# User_IO.net
KiCad netlist of a schematic drawn in Altium Designer
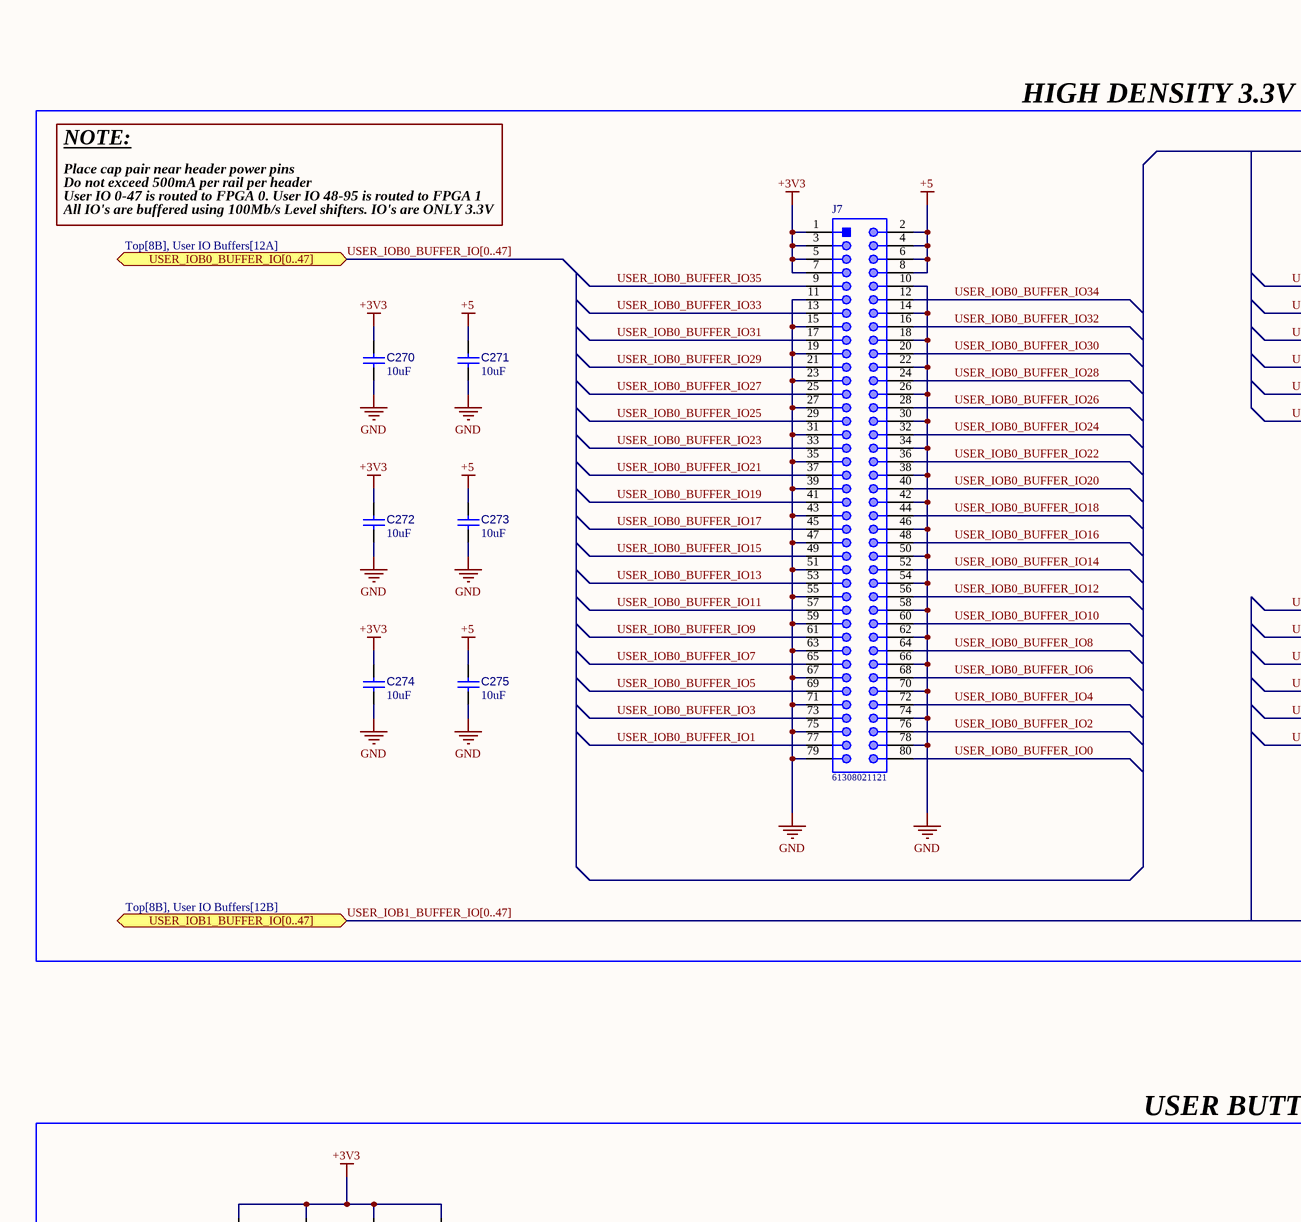
[diagram p0: User IO.SchDoc, top left]
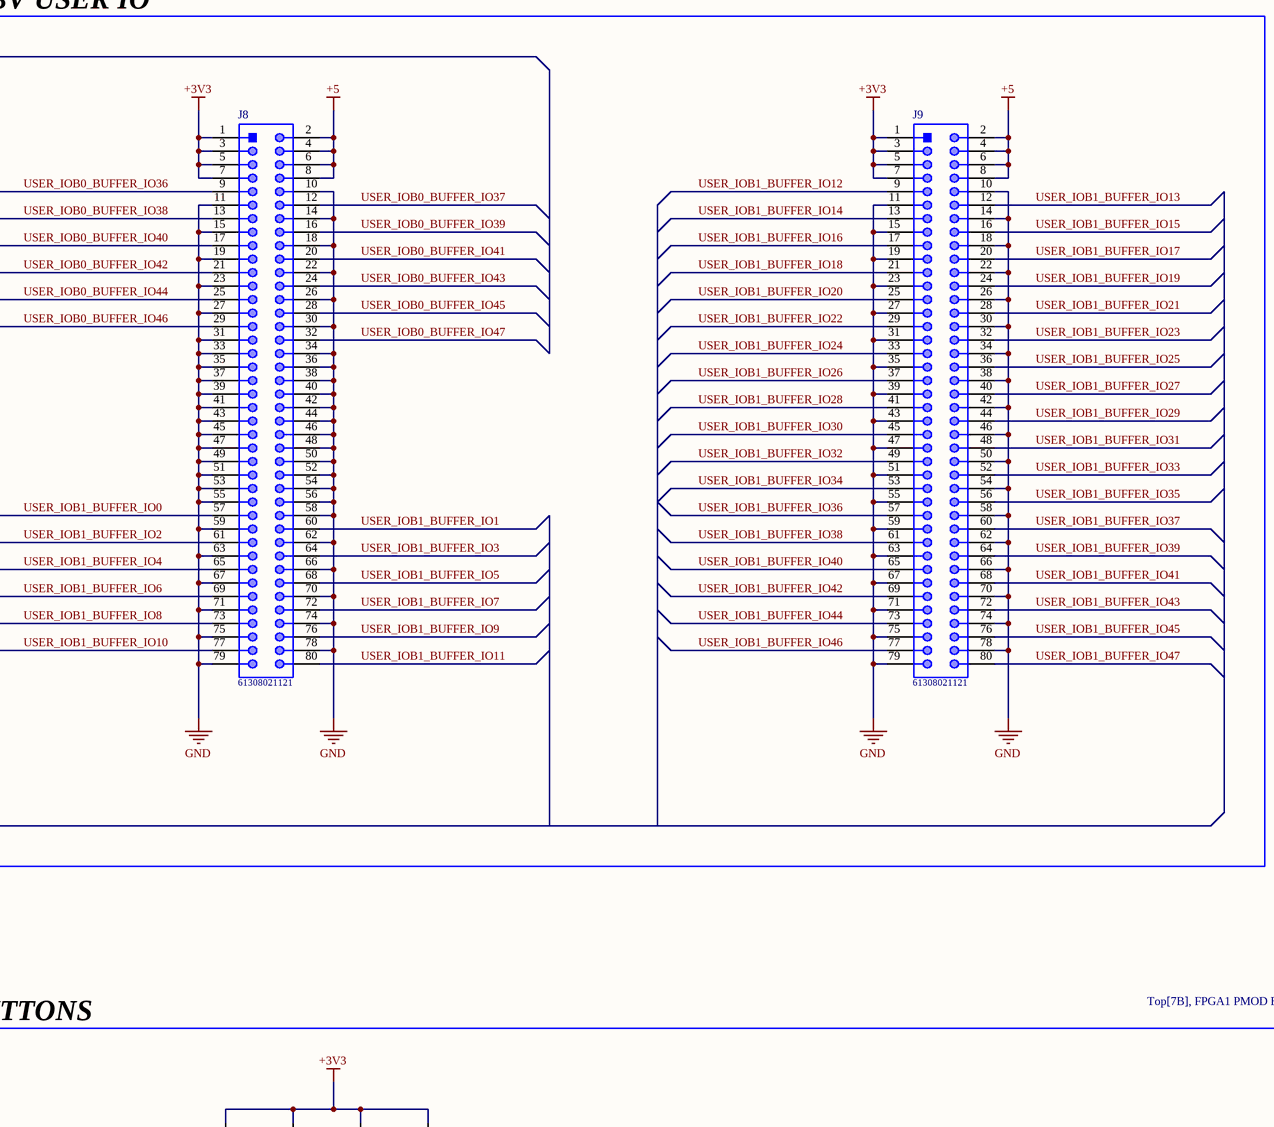
[diagram p1: User IO.SchDoc, top middle]
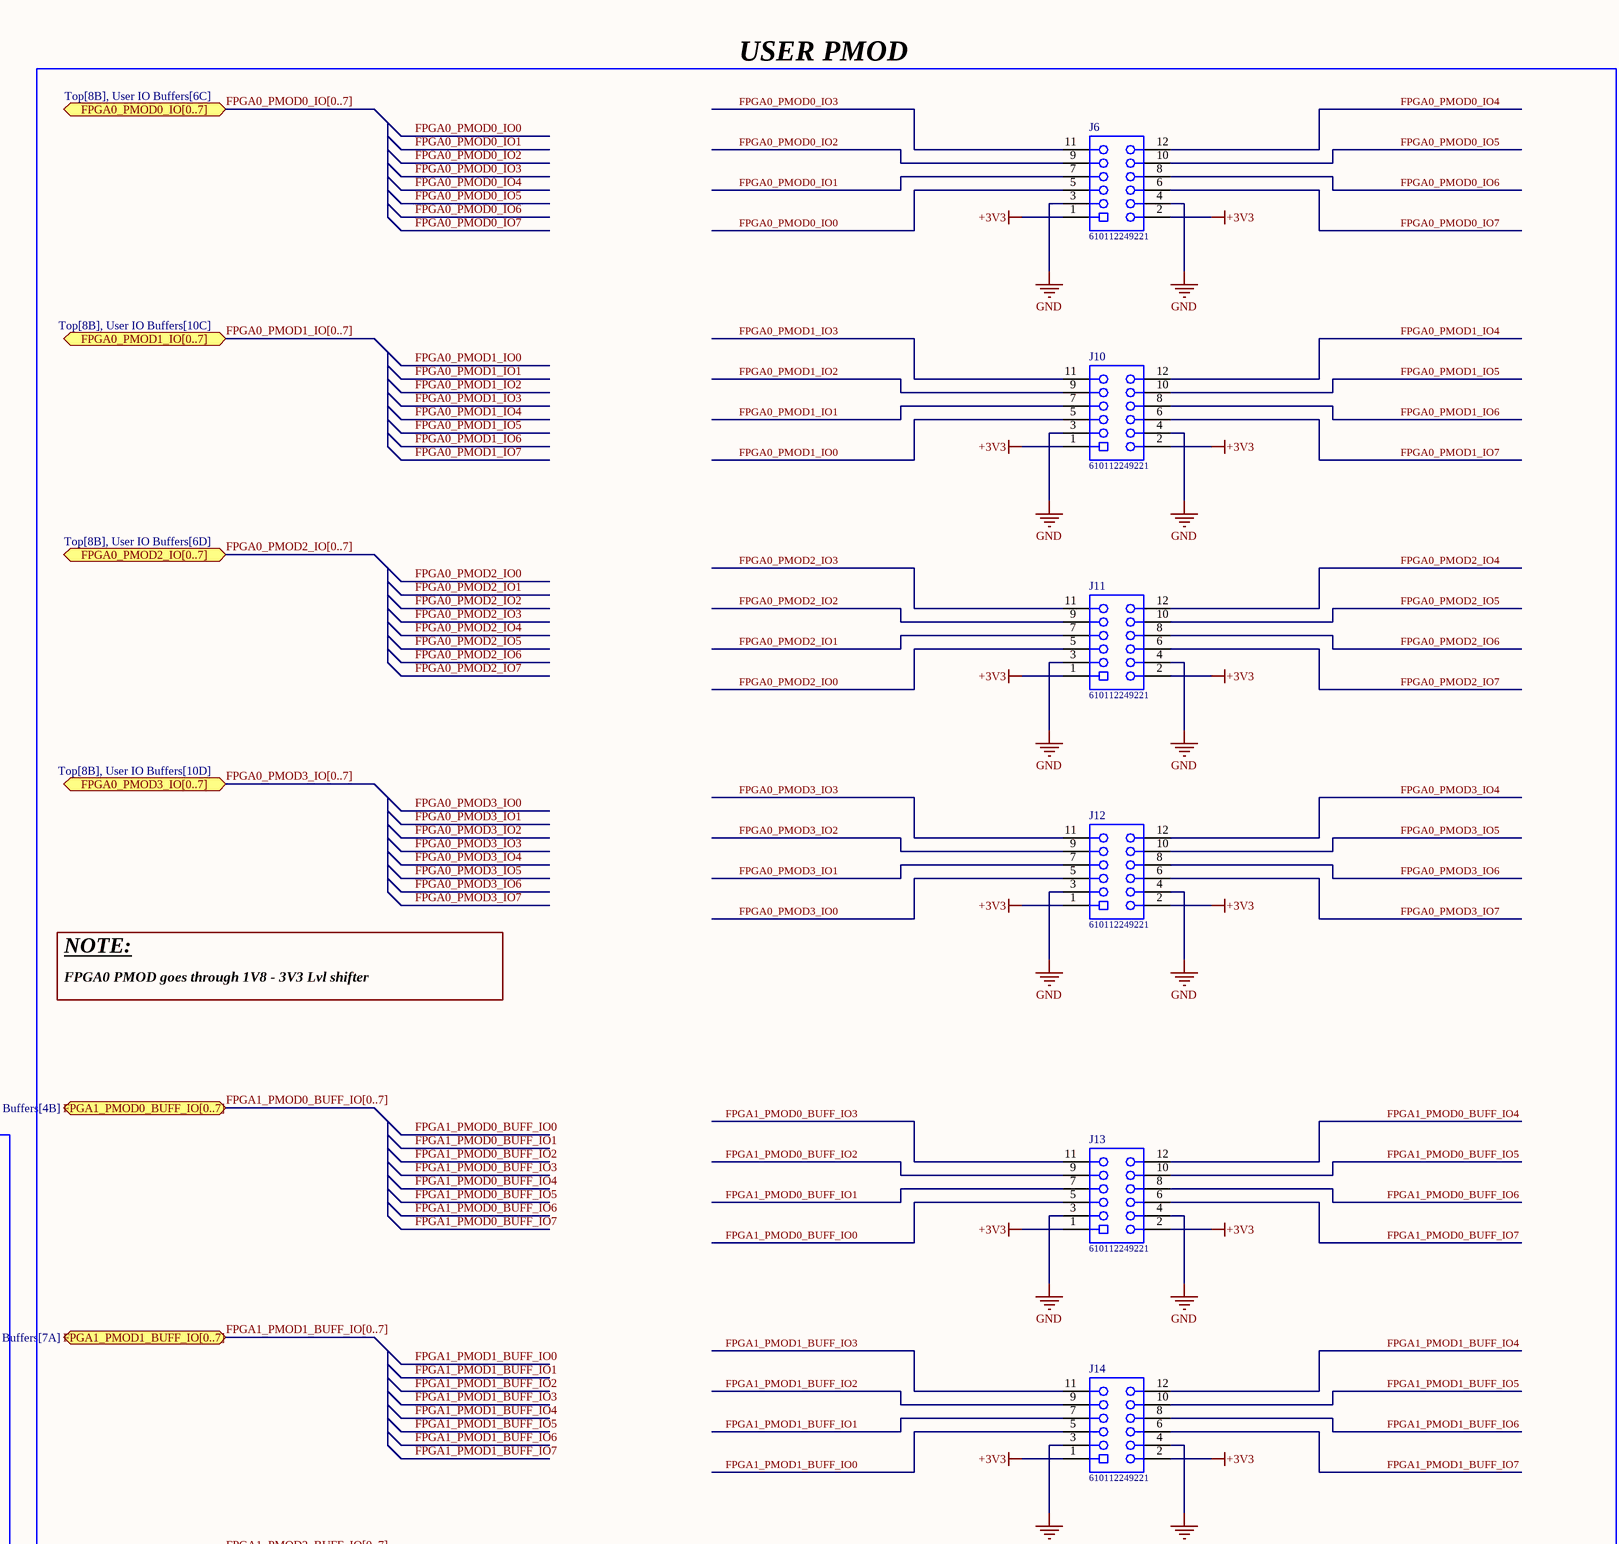
[diagram p2: User IO.SchDoc, top right]
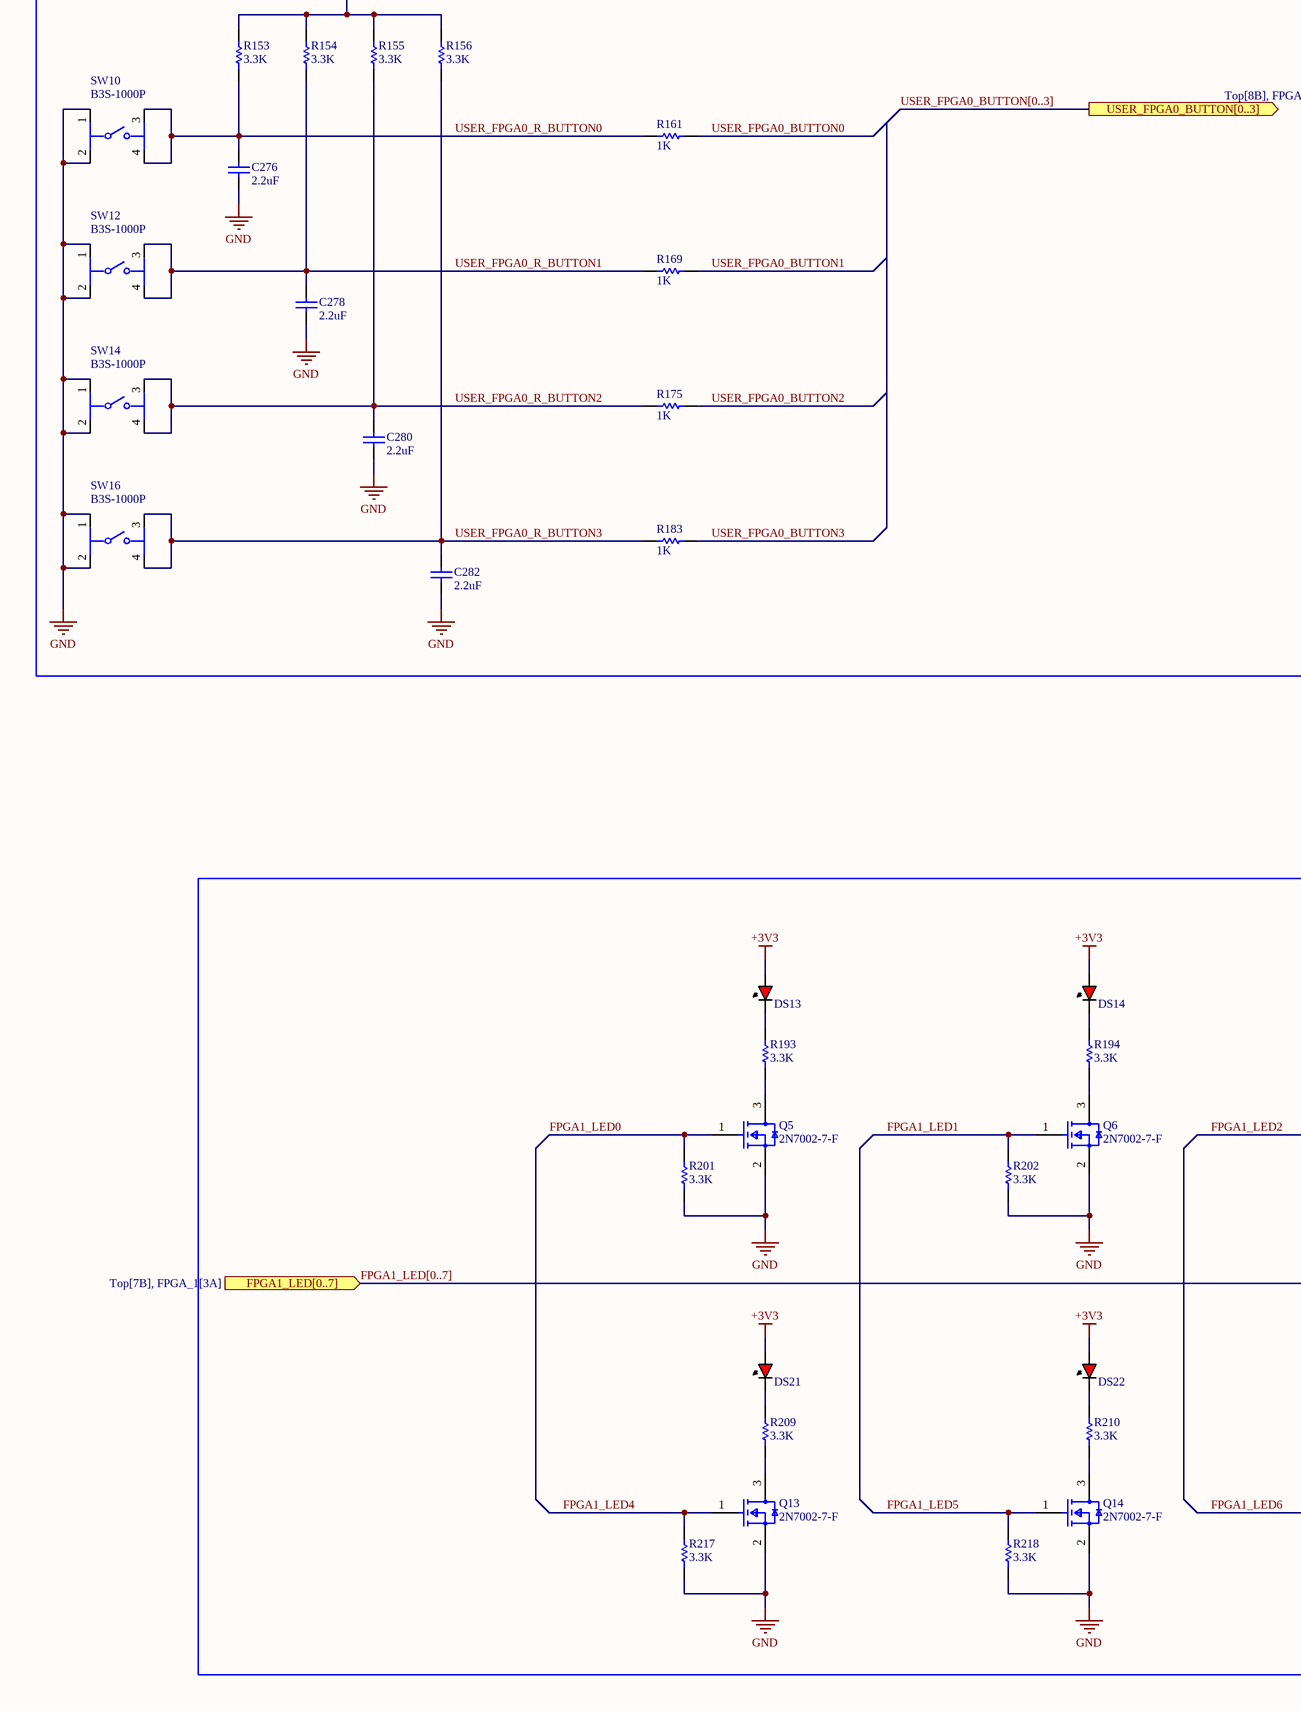
[diagram p3: User IO.SchDoc, bottom left]
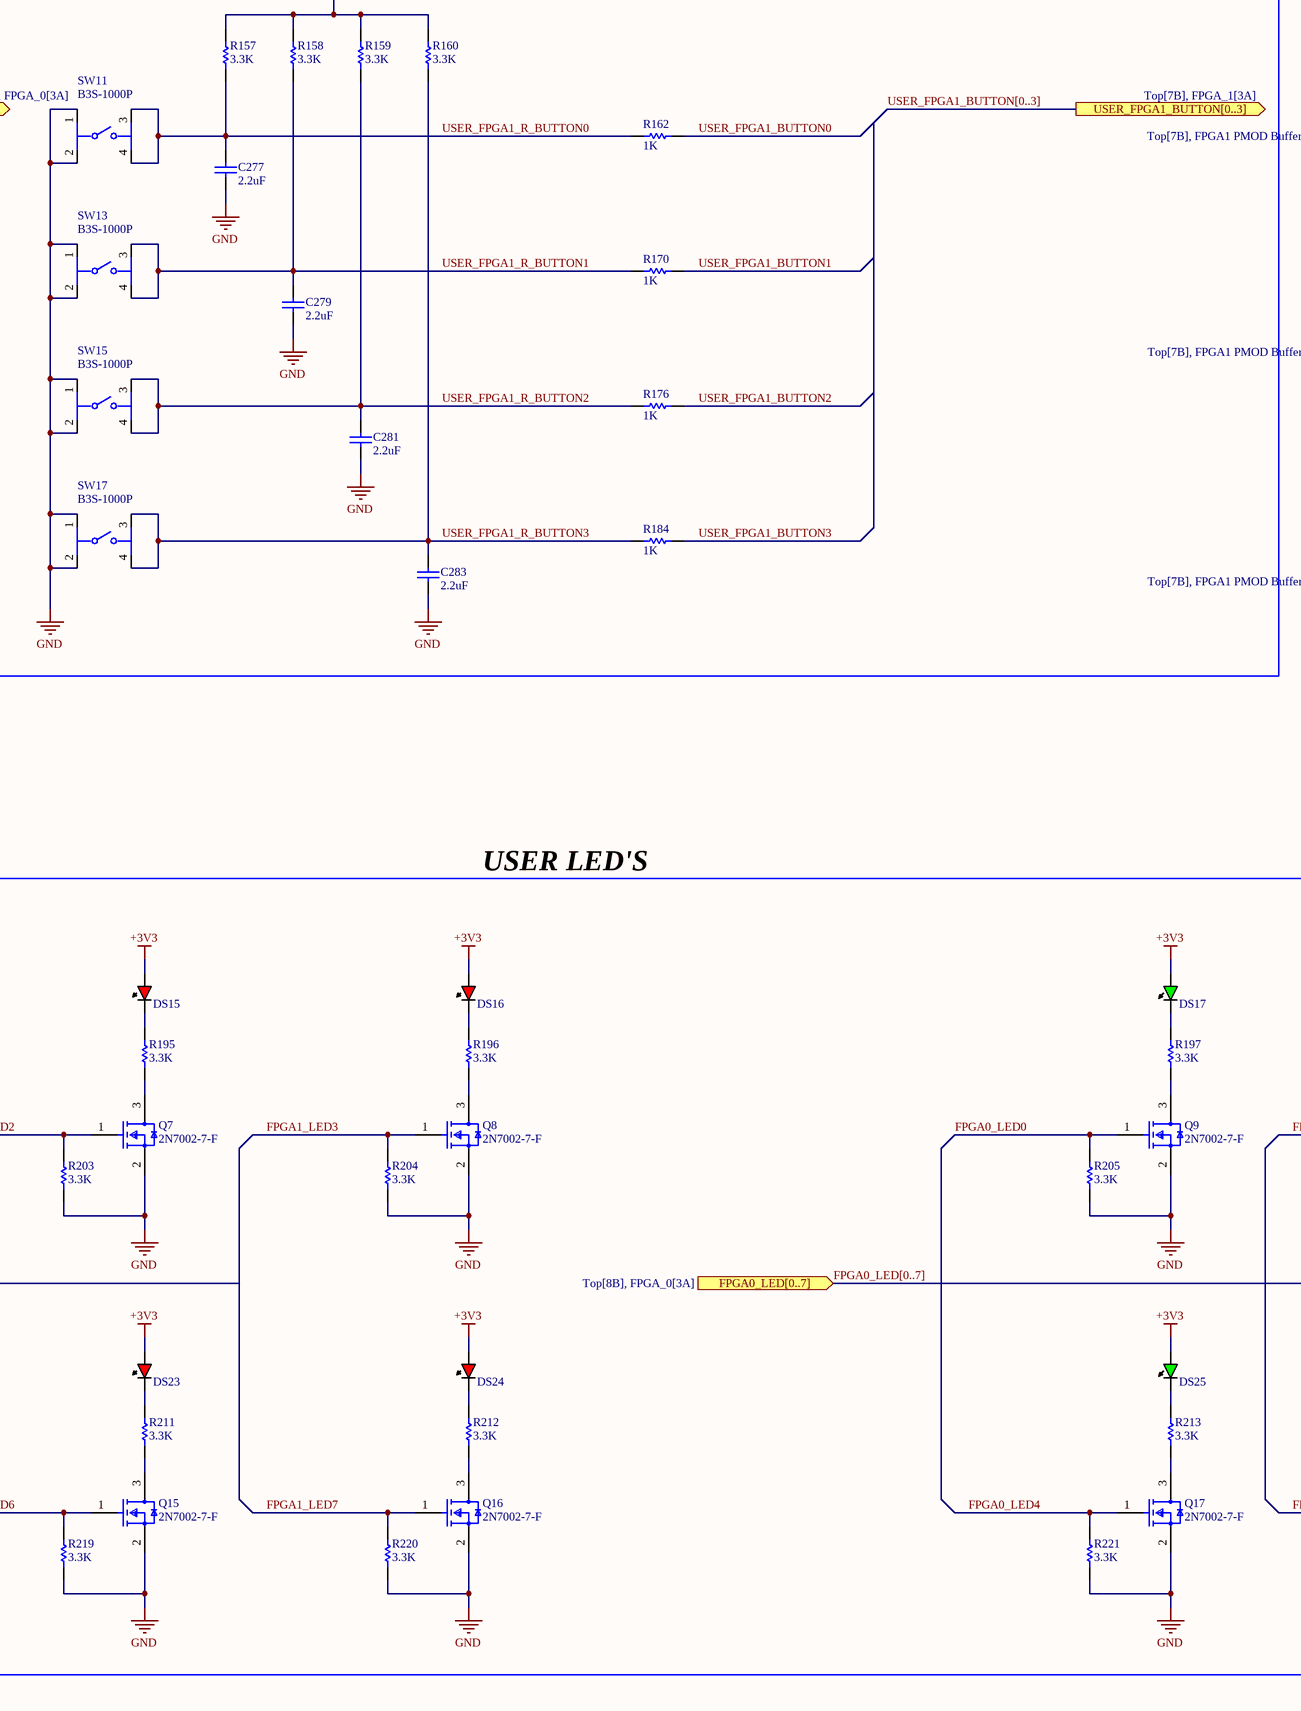
[diagram p4: User IO.SchDoc, bottom middle]
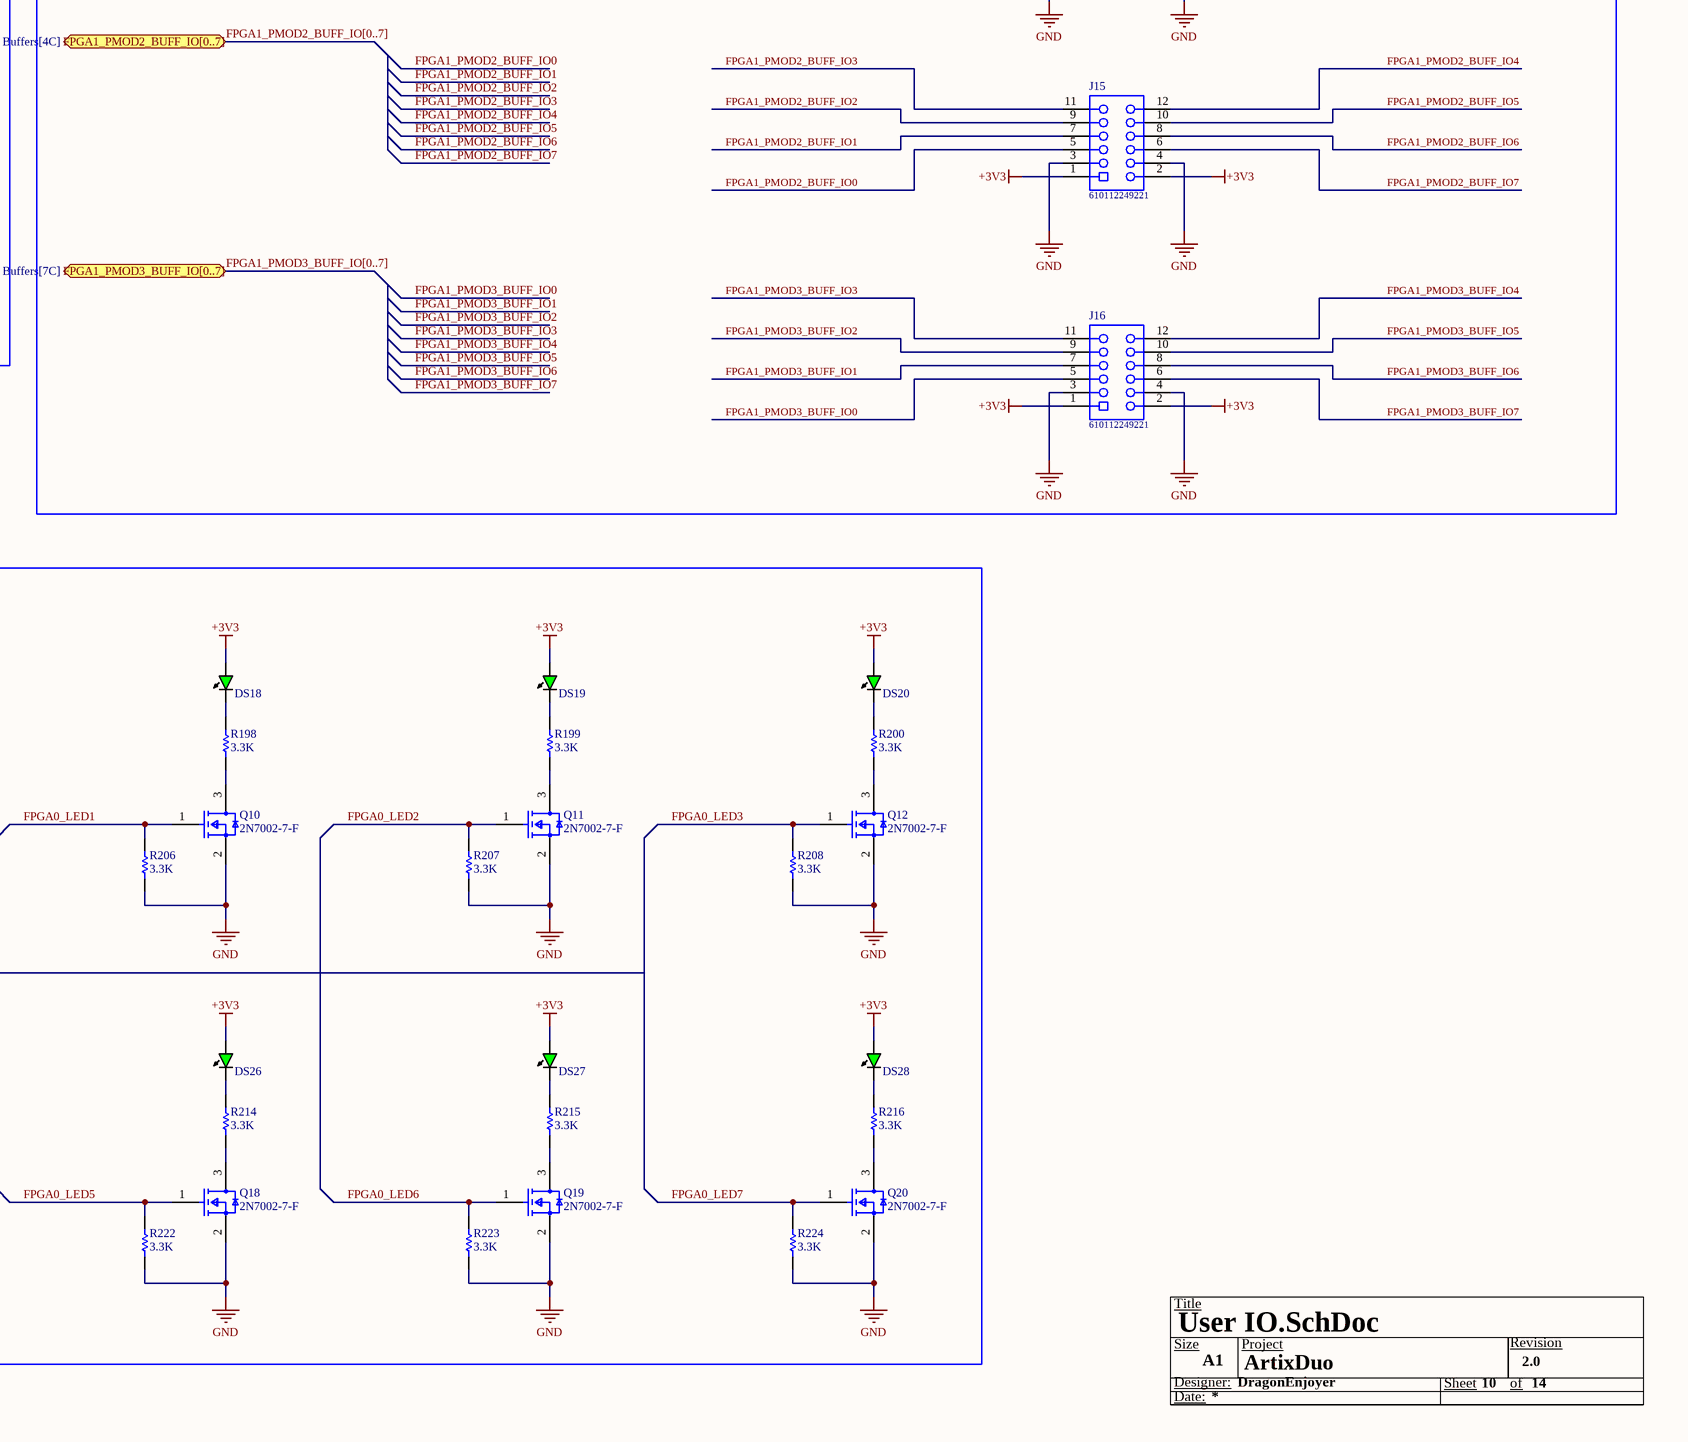
[diagram p5: User IO.SchDoc, bottom right]

(export (version "E")
  (design (tool "Eeschema 10.0.6"))
  (components
    (comp (ref "C270")
      (value "10uF")
      (footprint "CAPC1608X04N")
      (description "CAP CER 10UF 25V X5R 0603")
      (fields (field (name "VOLTAGE") "25V") (field (name "TOLERANCE") "20%"))
      (libsource (lib "Main Workspace") (part "CAP-NP-2"))
    )
    (comp (ref "C271")
      (value "10uF")
      (footprint "CAPC1608X04N")
      (description "CAP CER 10UF 25V X5R 0603")
      (fields (field (name "VOLTAGE") "25V") (field (name "TOLERANCE") "20%"))
      (libsource (lib "Main Workspace") (part "CAP-NP-2"))
    )
    (comp (ref "C272")
      (value "10uF")
      (footprint "CAPC1608X04N")
      (description "CAP CER 10UF 25V X5R 0603")
      (fields (field (name "VOLTAGE") "25V") (field (name "TOLERANCE") "20%"))
      (libsource (lib "Main Workspace") (part "CAP-NP-2"))
    )
    (comp (ref "C273")
      (value "10uF")
      (footprint "CAPC1608X04N")
      (description "CAP CER 10UF 25V X5R 0603")
      (fields (field (name "VOLTAGE") "25V") (field (name "TOLERANCE") "20%"))
      (libsource (lib "Main Workspace") (part "CAP-NP-2"))
    )
    (comp (ref "C274")
      (value "10uF")
      (footprint "CAPC1608X04N")
      (description "CAP CER 10UF 25V X5R 0603")
      (fields (field (name "VOLTAGE") "25V") (field (name "TOLERANCE") "20%"))
      (libsource (lib "Main Workspace") (part "CAP-NP-2"))
    )
    (comp (ref "C275")
      (value "10uF")
      (footprint "CAPC1608X04N")
      (description "CAP CER 10UF 25V X5R 0603")
      (fields (field (name "VOLTAGE") "25V") (field (name "TOLERANCE") "20%"))
      (libsource (lib "Main Workspace") (part "CAP-NP-2"))
    )
    (comp (ref "C276")
      (value "2.2uF")
      (footprint "CAPC1005X55X25NL05T10")
      (description "GRM155R60J225ME15D")
      (fields (field (name "MANUFACTURER") "Murata"))
      (libsource (lib "Altium Content Vault") (part "CAP"))
    )
    (comp (ref "C277")
      (value "2.2uF")
      (footprint "CAPC1005X55X25NL05T10")
      (description "GRM155R60J225ME15D")
      (fields (field (name "MANUFACTURER") "Murata"))
      (libsource (lib "Altium Content Vault") (part "CAP"))
    )
    (comp (ref "C278")
      (value "2.2uF")
      (footprint "CAPC1005X55X25NL05T10")
      (description "GRM155R60J225ME15D")
      (fields (field (name "MANUFACTURER") "Murata"))
      (libsource (lib "Altium Content Vault") (part "CAP"))
    )
    (comp (ref "C279")
      (value "2.2uF")
      (footprint "CAPC1005X55X25NL05T10")
      (description "GRM155R60J225ME15D")
      (fields (field (name "MANUFACTURER") "Murata"))
      (libsource (lib "Altium Content Vault") (part "CAP"))
    )
    (comp (ref "C280")
      (value "2.2uF")
      (footprint "CAPC1005X55X25NL05T10")
      (description "GRM155R60J225ME15D")
      (fields (field (name "MANUFACTURER") "Murata"))
      (libsource (lib "Altium Content Vault") (part "CAP"))
    )
    (comp (ref "C281")
      (value "2.2uF")
      (footprint "CAPC1005X55X25NL05T10")
      (description "GRM155R60J225ME15D")
      (fields (field (name "MANUFACTURER") "Murata"))
      (libsource (lib "Altium Content Vault") (part "CAP"))
    )
    (comp (ref "C282")
      (value "2.2uF")
      (footprint "CAPC1005X55X25NL05T10")
      (description "GRM155R60J225ME15D")
      (fields (field (name "MANUFACTURER") "Murata"))
      (libsource (lib "Altium Content Vault") (part "CAP"))
    )
    (comp (ref "C283")
      (value "2.2uF")
      (footprint "CAPC1005X55X25NL05T10")
      (description "GRM155R60J225ME15D")
      (fields (field (name "MANUFACTURER") "Murata"))
      (libsource (lib "Altium Content Vault") (part "CAP"))
    )
    (comp (ref "DS13")
      (value "TLMS1100-GS08")
      (footprint "VISH-TLMX1100_V")
      (description "LED Uni-Color Red 633nm Automotive 2-Pin Chip 0603(1608Metric) T/R")
      (libsource (lib "Main Workspace") (part "LED-RED-AK-2"))
    )
    (comp (ref "DS14")
      (value "TLMS1100-GS08")
      (footprint "VISH-TLMX1100_V")
      (description "LED Uni-Color Red 633nm Automotive 2-Pin Chip 0603(1608Metric) T/R")
      (libsource (lib "Main Workspace") (part "LED-RED-AK-2"))
    )
    (comp (ref "DS15")
      (value "TLMS1100-GS08")
      (footprint "VISH-TLMX1100_V")
      (description "LED Uni-Color Red 633nm Automotive 2-Pin Chip 0603(1608Metric) T/R")
      (libsource (lib "Main Workspace") (part "LED-RED-AK-2"))
    )
    (comp (ref "DS16")
      (value "TLMS1100-GS08")
      (footprint "VISH-TLMX1100_V")
      (description "LED Uni-Color Red 633nm Automotive 2-Pin Chip 0603(1608Metric) T/R")
      (libsource (lib "Main Workspace") (part "LED-RED-AK-2"))
    )
    (comp (ref "DS17")
      (value "SMLLX0603GWTR")
      (footprint "LUMX-SML-LX0603_V")
      (description "LED GREEN DIFFUSED SMD")
      (libsource (lib "Main Workspace") (part "LED-GREEN-AK-2"))
    )
    (comp (ref "DS18")
      (value "SMLLX0603GWTR")
      (footprint "LUMX-SML-LX0603_V")
      (description "LED GREEN DIFFUSED SMD")
      (libsource (lib "Main Workspace") (part "LED-GREEN-AK-2"))
    )
    (comp (ref "DS19")
      (value "SMLLX0603GWTR")
      (footprint "LUMX-SML-LX0603_V")
      (description "LED GREEN DIFFUSED SMD")
      (libsource (lib "Main Workspace") (part "LED-GREEN-AK-2"))
    )
    (comp (ref "DS20")
      (value "SMLLX0603GWTR")
      (footprint "LUMX-SML-LX0603_V")
      (description "LED GREEN DIFFUSED SMD")
      (libsource (lib "Main Workspace") (part "LED-GREEN-AK-2"))
    )
    (comp (ref "DS21")
      (value "TLMS1100-GS08")
      (footprint "VISH-TLMX1100_V")
      (description "LED Uni-Color Red 633nm Automotive 2-Pin Chip 0603(1608Metric) T/R")
      (libsource (lib "Main Workspace") (part "LED-RED-AK-2"))
    )
    (comp (ref "DS22")
      (value "TLMS1100-GS08")
      (footprint "VISH-TLMX1100_V")
      (description "LED Uni-Color Red 633nm Automotive 2-Pin Chip 0603(1608Metric) T/R")
      (libsource (lib "Main Workspace") (part "LED-RED-AK-2"))
    )
    (comp (ref "DS23")
      (value "TLMS1100-GS08")
      (footprint "VISH-TLMX1100_V")
      (description "LED Uni-Color Red 633nm Automotive 2-Pin Chip 0603(1608Metric) T/R")
      (libsource (lib "Main Workspace") (part "LED-RED-AK-2"))
    )
    (comp (ref "DS24")
      (value "TLMS1100-GS08")
      (footprint "VISH-TLMX1100_V")
      (description "LED Uni-Color Red 633nm Automotive 2-Pin Chip 0603(1608Metric) T/R")
      (libsource (lib "Main Workspace") (part "LED-RED-AK-2"))
    )
    (comp (ref "DS25")
      (value "SMLLX0603GWTR")
      (footprint "LUMX-SML-LX0603_V")
      (description "LED GREEN DIFFUSED SMD")
      (libsource (lib "Main Workspace") (part "LED-GREEN-AK-2"))
    )
    (comp (ref "DS26")
      (value "SMLLX0603GWTR")
      (footprint "LUMX-SML-LX0603_V")
      (description "LED GREEN DIFFUSED SMD")
      (libsource (lib "Main Workspace") (part "LED-GREEN-AK-2"))
    )
    (comp (ref "DS27")
      (value "SMLLX0603GWTR")
      (footprint "LUMX-SML-LX0603_V")
      (description "LED GREEN DIFFUSED SMD")
      (libsource (lib "Main Workspace") (part "LED-GREEN-AK-2"))
    )
    (comp (ref "DS28")
      (value "SMLLX0603GWTR")
      (footprint "LUMX-SML-LX0603_V")
      (description "LED GREEN DIFFUSED SMD")
      (libsource (lib "Main Workspace") (part "LED-GREEN-AK-2"))
    )
    (comp (ref "J6")
      (value "610112249221")
      (footprint "610112249221")
      (description "SMT Angled Socket Header WR-PHD, Pitch 2.54 mm, Dual Row, 12 pins")
      (fields (field (name "MANUFACTURER") "Wurth Elektronik") (field (name "PUBLISHER") "WurthElektronik"))
      (libsource (lib "Altium Content Vault") (part "WE-CN-2P-F-R12"))
    )
    (comp (ref "J7")
      (value "61308021121")
      (footprint "61308021121")
      (description "THT Vertical Pin Header WR-PHD, Pitch 2.54 mm, Dual Row, 80 pins")
      (fields (field (name "MANUFACTURER") "Wurth Elektronik") (field (name "PUBLISHER") "WurthElektronik"))
      (libsource (lib "Altium Content Vault") (part "WE-CN-2P-M-R80"))
    )
    (comp (ref "J8")
      (value "61308021121")
      (footprint "61308021121")
      (description "THT Vertical Pin Header WR-PHD, Pitch 2.54 mm, Dual Row, 80 pins")
      (fields (field (name "MANUFACTURER") "Wurth Elektronik") (field (name "PUBLISHER") "WurthElektronik"))
      (libsource (lib "Altium Content Vault") (part "WE-CN-2P-M-R80"))
    )
    (comp (ref "J9")
      (value "61308021121")
      (footprint "61308021121")
      (description "THT Vertical Pin Header WR-PHD, Pitch 2.54 mm, Dual Row, 80 pins")
      (fields (field (name "MANUFACTURER") "Wurth Elektronik") (field (name "PUBLISHER") "WurthElektronik"))
      (libsource (lib "Altium Content Vault") (part "WE-CN-2P-M-R80"))
    )
    (comp (ref "J10")
      (value "610112249221")
      (footprint "610112249221")
      (description "SMT Angled Socket Header WR-PHD, Pitch 2.54 mm, Dual Row, 12 pins")
      (fields (field (name "MANUFACTURER") "Wurth Elektronik") (field (name "PUBLISHER") "WurthElektronik"))
      (libsource (lib "Altium Content Vault") (part "WE-CN-2P-F-R12"))
    )
    (comp (ref "J11")
      (value "610112249221")
      (footprint "610112249221")
      (description "SMT Angled Socket Header WR-PHD, Pitch 2.54 mm, Dual Row, 12 pins")
      (fields (field (name "MANUFACTURER") "Wurth Elektronik") (field (name "PUBLISHER") "WurthElektronik"))
      (libsource (lib "Altium Content Vault") (part "WE-CN-2P-F-R12"))
    )
    (comp (ref "J12")
      (value "610112249221")
      (footprint "610112249221")
      (description "SMT Angled Socket Header WR-PHD, Pitch 2.54 mm, Dual Row, 12 pins")
      (fields (field (name "MANUFACTURER") "Wurth Elektronik") (field (name "PUBLISHER") "WurthElektronik"))
      (libsource (lib "Altium Content Vault") (part "WE-CN-2P-F-R12"))
    )
    (comp (ref "J13")
      (value "610112249221")
      (footprint "610112249221")
      (description "SMT Angled Socket Header WR-PHD, Pitch 2.54 mm, Dual Row, 12 pins")
      (fields (field (name "MANUFACTURER") "Wurth Elektronik") (field (name "PUBLISHER") "WurthElektronik"))
      (libsource (lib "Altium Content Vault") (part "WE-CN-2P-F-R12"))
    )
    (comp (ref "J14")
      (value "610112249221")
      (footprint "610112249221")
      (description "SMT Angled Socket Header WR-PHD, Pitch 2.54 mm, Dual Row, 12 pins")
      (fields (field (name "MANUFACTURER") "Wurth Elektronik") (field (name "PUBLISHER") "WurthElektronik"))
      (libsource (lib "Altium Content Vault") (part "WE-CN-2P-F-R12"))
    )
    (comp (ref "J15")
      (value "610112249221")
      (footprint "610112249221")
      (description "SMT Angled Socket Header WR-PHD, Pitch 2.54 mm, Dual Row, 12 pins")
      (fields (field (name "MANUFACTURER") "Wurth Elektronik") (field (name "PUBLISHER") "WurthElektronik"))
      (libsource (lib "Altium Content Vault") (part "WE-CN-2P-F-R12"))
    )
    (comp (ref "J16")
      (value "610112249221")
      (footprint "610112249221")
      (description "SMT Angled Socket Header WR-PHD, Pitch 2.54 mm, Dual Row, 12 pins")
      (fields (field (name "MANUFACTURER") "Wurth Elektronik") (field (name "PUBLISHER") "WurthElektronik"))
      (libsource (lib "Altium Content Vault") (part "WE-CN-2P-F-R12"))
    )
    (comp (ref "Q5")
      (value "2N7002-7-F")
      (footprint "FP-SOT23-MFG")
      (description "MOSFET N-CH 60V 115MA SOT23-3")
      (fields (field (name "VOLTAGE") "60V"))
      (libsource (lib "Altium Content Vault") (part "3b9c635fedb024a5347a57b145af9cc"))
    )
    (comp (ref "Q6")
      (value "2N7002-7-F")
      (footprint "FP-SOT23-MFG")
      (description "MOSFET N-CH 60V 115MA SOT23-3")
      (fields (field (name "VOLTAGE") "60V"))
      (libsource (lib "Altium Content Vault") (part "3b9c635fedb024a5347a57b145af9cc"))
    )
    (comp (ref "Q7")
      (value "2N7002-7-F")
      (footprint "FP-SOT23-MFG")
      (description "MOSFET N-CH 60V 115MA SOT23-3")
      (fields (field (name "VOLTAGE") "60V"))
      (libsource (lib "Altium Content Vault") (part "3b9c635fedb024a5347a57b145af9cc"))
    )
    (comp (ref "Q8")
      (value "2N7002-7-F")
      (footprint "FP-SOT23-MFG")
      (description "MOSFET N-CH 60V 115MA SOT23-3")
      (fields (field (name "VOLTAGE") "60V"))
      (libsource (lib "Altium Content Vault") (part "3b9c635fedb024a5347a57b145af9cc"))
    )
    (comp (ref "Q9")
      (value "2N7002-7-F")
      (footprint "FP-SOT23-MFG")
      (description "MOSFET N-CH 60V 115MA SOT23-3")
      (fields (field (name "VOLTAGE") "60V"))
      (libsource (lib "Altium Content Vault") (part "3b9c635fedb024a5347a57b145af9cc"))
    )
    (comp (ref "Q10")
      (value "2N7002-7-F")
      (footprint "FP-SOT23-MFG")
      (description "MOSFET N-CH 60V 115MA SOT23-3")
      (fields (field (name "VOLTAGE") "60V"))
      (libsource (lib "Altium Content Vault") (part "3b9c635fedb024a5347a57b145af9cc"))
    )
    (comp (ref "Q11")
      (value "2N7002-7-F")
      (footprint "FP-SOT23-MFG")
      (description "MOSFET N-CH 60V 115MA SOT23-3")
      (fields (field (name "VOLTAGE") "60V"))
      (libsource (lib "Altium Content Vault") (part "3b9c635fedb024a5347a57b145af9cc"))
    )
    (comp (ref "Q12")
      (value "2N7002-7-F")
      (footprint "FP-SOT23-MFG")
      (description "MOSFET N-CH 60V 115MA SOT23-3")
      (fields (field (name "VOLTAGE") "60V"))
      (libsource (lib "Altium Content Vault") (part "3b9c635fedb024a5347a57b145af9cc"))
    )
    (comp (ref "Q13")
      (value "2N7002-7-F")
      (footprint "FP-SOT23-MFG")
      (description "MOSFET N-CH 60V 115MA SOT23-3")
      (fields (field (name "VOLTAGE") "60V"))
      (libsource (lib "Altium Content Vault") (part "3b9c635fedb024a5347a57b145af9cc"))
    )
    (comp (ref "Q14")
      (value "2N7002-7-F")
      (footprint "FP-SOT23-MFG")
      (description "MOSFET N-CH 60V 115MA SOT23-3")
      (fields (field (name "VOLTAGE") "60V"))
      (libsource (lib "Altium Content Vault") (part "3b9c635fedb024a5347a57b145af9cc"))
    )
    (comp (ref "Q15")
      (value "2N7002-7-F")
      (footprint "FP-SOT23-MFG")
      (description "MOSFET N-CH 60V 115MA SOT23-3")
      (fields (field (name "VOLTAGE") "60V"))
      (libsource (lib "Altium Content Vault") (part "3b9c635fedb024a5347a57b145af9cc"))
    )
    (comp (ref "Q16")
      (value "2N7002-7-F")
      (footprint "FP-SOT23-MFG")
      (description "MOSFET N-CH 60V 115MA SOT23-3")
      (fields (field (name "VOLTAGE") "60V"))
      (libsource (lib "Altium Content Vault") (part "3b9c635fedb024a5347a57b145af9cc"))
    )
    (comp (ref "Q17")
      (value "2N7002-7-F")
      (footprint "FP-SOT23-MFG")
      (description "MOSFET N-CH 60V 115MA SOT23-3")
      (fields (field (name "VOLTAGE") "60V"))
      (libsource (lib "Altium Content Vault") (part "3b9c635fedb024a5347a57b145af9cc"))
    )
    (comp (ref "Q18")
      (value "2N7002-7-F")
      (footprint "FP-SOT23-MFG")
      (description "MOSFET N-CH 60V 115MA SOT23-3")
      (fields (field (name "VOLTAGE") "60V"))
      (libsource (lib "Altium Content Vault") (part "3b9c635fedb024a5347a57b145af9cc"))
    )
    (comp (ref "Q19")
      (value "2N7002-7-F")
      (footprint "FP-SOT23-MFG")
      (description "MOSFET N-CH 60V 115MA SOT23-3")
      (fields (field (name "VOLTAGE") "60V"))
      (libsource (lib "Altium Content Vault") (part "3b9c635fedb024a5347a57b145af9cc"))
    )
    (comp (ref "Q20")
      (value "2N7002-7-F")
      (footprint "FP-SOT23-MFG")
      (description "MOSFET N-CH 60V 115MA SOT23-3")
      (fields (field (name "VOLTAGE") "60V"))
      (libsource (lib "Altium Content Vault") (part "3b9c635fedb024a5347a57b145af9cc"))
    )
    (comp (ref "R153")
      (value "3.3K")
      (footprint "RESC1005X40X25NL05T10")
      (description "CRCW04023K30FKEDHP")
      (fields (field (name "MANUFACTURER") "Vishay Dale"))
      (libsource (lib "Altium Content Vault") (part "RES"))
    )
    (comp (ref "R154")
      (value "3.3K")
      (footprint "RESC1005X40X25NL05T10")
      (description "CRCW04023K30FKEDHP")
      (fields (field (name "MANUFACTURER") "Vishay Dale"))
      (libsource (lib "Altium Content Vault") (part "RES"))
    )
    (comp (ref "R155")
      (value "3.3K")
      (footprint "RESC1005X40X25NL05T10")
      (description "CRCW04023K30FKEDHP")
      (fields (field (name "MANUFACTURER") "Vishay Dale"))
      (libsource (lib "Altium Content Vault") (part "RES"))
    )
    (comp (ref "R156")
      (value "3.3K")
      (footprint "RESC1005X40X25NL05T10")
      (description "CRCW04023K30FKEDHP")
      (fields (field (name "MANUFACTURER") "Vishay Dale"))
      (libsource (lib "Altium Content Vault") (part "RES"))
    )
    (comp (ref "R157")
      (value "3.3K")
      (footprint "RESC1005X40X25NL05T10")
      (description "CRCW04023K30FKEDHP")
      (fields (field (name "MANUFACTURER") "Vishay Dale"))
      (libsource (lib "Altium Content Vault") (part "RES"))
    )
    (comp (ref "R158")
      (value "3.3K")
      (footprint "RESC1005X40X25NL05T10")
      (description "CRCW04023K30FKEDHP")
      (fields (field (name "MANUFACTURER") "Vishay Dale"))
      (libsource (lib "Altium Content Vault") (part "RES"))
    )
    (comp (ref "R159")
      (value "3.3K")
      (footprint "RESC1005X40X25NL05T10")
      (description "CRCW04023K30FKEDHP")
      (fields (field (name "MANUFACTURER") "Vishay Dale"))
      (libsource (lib "Altium Content Vault") (part "RES"))
    )
    (comp (ref "R160")
      (value "3.3K")
      (footprint "RESC1005X40X25NL05T10")
      (description "CRCW04023K30FKEDHP")
      (fields (field (name "MANUFACTURER") "Vishay Dale"))
      (libsource (lib "Altium Content Vault") (part "RES"))
    )
    (comp (ref "R161")
      (value "1K")
      (footprint "RESC1005X40X25NL05T10")
      (description "CRCW04021K00FKEDHP")
      (fields (field (name "MANUFACTURER") "Vishay Dale"))
      (libsource (lib "Altium Content Vault") (part "RES"))
    )
    (comp (ref "R162")
      (value "1K")
      (footprint "RESC1005X40X25NL05T10")
      (description "CRCW04021K00FKEDHP")
      (fields (field (name "MANUFACTURER") "Vishay Dale"))
      (libsource (lib "Altium Content Vault") (part "RES"))
    )
    (comp (ref "R169")
      (value "1K")
      (footprint "RESC1005X40X25NL05T10")
      (description "CRCW04021K00FKEDHP")
      (fields (field (name "MANUFACTURER") "Vishay Dale"))
      (libsource (lib "Altium Content Vault") (part "RES"))
    )
    (comp (ref "R170")
      (value "1K")
      (footprint "RESC1005X40X25NL05T10")
      (description "CRCW04021K00FKEDHP")
      (fields (field (name "MANUFACTURER") "Vishay Dale"))
      (libsource (lib "Altium Content Vault") (part "RES"))
    )
    (comp (ref "R175")
      (value "1K")
      (footprint "RESC1005X40X25NL05T10")
      (description "CRCW04021K00FKEDHP")
      (fields (field (name "MANUFACTURER") "Vishay Dale"))
      (libsource (lib "Altium Content Vault") (part "RES"))
    )
    (comp (ref "R176")
      (value "1K")
      (footprint "RESC1005X40X25NL05T10")
      (description "CRCW04021K00FKEDHP")
      (fields (field (name "MANUFACTURER") "Vishay Dale"))
      (libsource (lib "Altium Content Vault") (part "RES"))
    )
    (comp (ref "R183")
      (value "1K")
      (footprint "RESC1005X40X25NL05T10")
      (description "CRCW04021K00FKEDHP")
      (fields (field (name "MANUFACTURER") "Vishay Dale"))
      (libsource (lib "Altium Content Vault") (part "RES"))
    )
    (comp (ref "R184")
      (value "1K")
      (footprint "RESC1005X40X25NL05T10")
      (description "CRCW04021K00FKEDHP")
      (fields (field (name "MANUFACTURER") "Vishay Dale"))
      (libsource (lib "Altium Content Vault") (part "RES"))
    )
    (comp (ref "R193")
      (value "3.3K")
      (footprint "RESC1005X40X25NL05T10")
      (description "CRCW04023K30FKEDHP")
      (fields (field (name "MANUFACTURER") "Vishay Dale"))
      (libsource (lib "Altium Content Vault") (part "RES"))
    )
    (comp (ref "R194")
      (value "3.3K")
      (footprint "RESC1005X40X25NL05T10")
      (description "CRCW04023K30FKEDHP")
      (fields (field (name "MANUFACTURER") "Vishay Dale"))
      (libsource (lib "Altium Content Vault") (part "RES"))
    )
    (comp (ref "R195")
      (value "3.3K")
      (footprint "RESC1005X40X25NL05T10")
      (description "CRCW04023K30FKEDHP")
      (fields (field (name "MANUFACTURER") "Vishay Dale"))
      (libsource (lib "Altium Content Vault") (part "RES"))
    )
    (comp (ref "R196")
      (value "3.3K")
      (footprint "RESC1005X40X25NL05T10")
      (description "CRCW04023K30FKEDHP")
      (fields (field (name "MANUFACTURER") "Vishay Dale"))
      (libsource (lib "Altium Content Vault") (part "RES"))
    )
    (comp (ref "R197")
      (value "3.3K")
      (footprint "RESC1005X40X25NL05T10")
      (description "CRCW04023K30FKEDHP")
      (fields (field (name "MANUFACTURER") "Vishay Dale"))
      (libsource (lib "Altium Content Vault") (part "RES"))
    )
    (comp (ref "R198")
      (value "3.3K")
      (footprint "RESC1005X40X25NL05T10")
      (description "CRCW04023K30FKEDHP")
      (fields (field (name "MANUFACTURER") "Vishay Dale"))
      (libsource (lib "Altium Content Vault") (part "RES"))
    )
    (comp (ref "R199")
      (value "3.3K")
      (footprint "RESC1005X40X25NL05T10")
      (description "CRCW04023K30FKEDHP")
      (fields (field (name "MANUFACTURER") "Vishay Dale"))
      (libsource (lib "Altium Content Vault") (part "RES"))
    )
    (comp (ref "R200")
      (value "3.3K")
      (footprint "RESC1005X40X25NL05T10")
      (description "CRCW04023K30FKEDHP")
      (fields (field (name "MANUFACTURER") "Vishay Dale"))
      (libsource (lib "Altium Content Vault") (part "RES"))
    )
    (comp (ref "R201")
      (value "3.3K")
      (footprint "RESC1005X40X25NL05T10")
      (description "CRCW04023K30FKEDHP")
      (fields (field (name "MANUFACTURER") "Vishay Dale"))
      (libsource (lib "Altium Content Vault") (part "RES"))
    )
    (comp (ref "R202")
      (value "3.3K")
      (footprint "RESC1005X40X25NL05T10")
      (description "CRCW04023K30FKEDHP")
      (fields (field (name "MANUFACTURER") "Vishay Dale"))
      (libsource (lib "Altium Content Vault") (part "RES"))
    )
    (comp (ref "R203")
      (value "3.3K")
      (footprint "RESC1005X40X25NL05T10")
      (description "CRCW04023K30FKEDHP")
      (fields (field (name "MANUFACTURER") "Vishay Dale"))
      (libsource (lib "Altium Content Vault") (part "RES"))
    )
    (comp (ref "R204")
      (value "3.3K")
      (footprint "RESC1005X40X25NL05T10")
      (description "CRCW04023K30FKEDHP")
      (fields (field (name "MANUFACTURER") "Vishay Dale"))
      (libsource (lib "Altium Content Vault") (part "RES"))
    )
    (comp (ref "R205")
      (value "3.3K")
      (footprint "RESC1005X40X25NL05T10")
      (description "CRCW04023K30FKEDHP")
      (fields (field (name "MANUFACTURER") "Vishay Dale"))
      (libsource (lib "Altium Content Vault") (part "RES"))
    )
    (comp (ref "R206")
      (value "3.3K")
      (footprint "RESC1005X40X25NL05T10")
      (description "CRCW04023K30FKEDHP")
      (fields (field (name "MANUFACTURER") "Vishay Dale"))
      (libsource (lib "Altium Content Vault") (part "RES"))
    )
    (comp (ref "R207")
      (value "3.3K")
      (footprint "RESC1005X40X25NL05T10")
      (description "CRCW04023K30FKEDHP")
      (fields (field (name "MANUFACTURER") "Vishay Dale"))
      (libsource (lib "Altium Content Vault") (part "RES"))
    )
    (comp (ref "R208")
      (value "3.3K")
      (footprint "RESC1005X40X25NL05T10")
      (description "CRCW04023K30FKEDHP")
      (fields (field (name "MANUFACTURER") "Vishay Dale"))
      (libsource (lib "Altium Content Vault") (part "RES"))
    )
    (comp (ref "R209")
      (value "3.3K")
      (footprint "RESC1005X40X25NL05T10")
      (description "CRCW04023K30FKEDHP")
      (fields (field (name "MANUFACTURER") "Vishay Dale"))
      (libsource (lib "Altium Content Vault") (part "RES"))
    )
    (comp (ref "R210")
      (value "3.3K")
      (footprint "RESC1005X40X25NL05T10")
      (description "CRCW04023K30FKEDHP")
      (fields (field (name "MANUFACTURER") "Vishay Dale"))
      (libsource (lib "Altium Content Vault") (part "RES"))
    )
    (comp (ref "R211")
      (value "3.3K")
      (footprint "RESC1005X40X25NL05T10")
      (description "CRCW04023K30FKEDHP")
      (fields (field (name "MANUFACTURER") "Vishay Dale"))
      (libsource (lib "Altium Content Vault") (part "RES"))
    )
    (comp (ref "R212")
      (value "3.3K")
      (footprint "RESC1005X40X25NL05T10")
      (description "CRCW04023K30FKEDHP")
      (fields (field (name "MANUFACTURER") "Vishay Dale"))
      (libsource (lib "Altium Content Vault") (part "RES"))
    )
    (comp (ref "R213")
      (value "3.3K")
      (footprint "RESC1005X40X25NL05T10")
      (description "CRCW04023K30FKEDHP")
      (fields (field (name "MANUFACTURER") "Vishay Dale"))
      (libsource (lib "Altium Content Vault") (part "RES"))
    )
    (comp (ref "R214")
      (value "3.3K")
      (footprint "RESC1005X40X25NL05T10")
      (description "CRCW04023K30FKEDHP")
      (fields (field (name "MANUFACTURER") "Vishay Dale"))
      (libsource (lib "Altium Content Vault") (part "RES"))
    )
    (comp (ref "R215")
      (value "3.3K")
      (footprint "RESC1005X40X25NL05T10")
      (description "CRCW04023K30FKEDHP")
      (fields (field (name "MANUFACTURER") "Vishay Dale"))
      (libsource (lib "Altium Content Vault") (part "RES"))
    )
    (comp (ref "R216")
      (value "3.3K")
      (footprint "RESC1005X40X25NL05T10")
      (description "CRCW04023K30FKEDHP")
      (fields (field (name "MANUFACTURER") "Vishay Dale"))
      (libsource (lib "Altium Content Vault") (part "RES"))
    )
    (comp (ref "R217")
      (value "3.3K")
      (footprint "RESC1005X40X25NL05T10")
      (description "CRCW04023K30FKEDHP")
      (fields (field (name "MANUFACTURER") "Vishay Dale"))
      (libsource (lib "Altium Content Vault") (part "RES"))
    )
    (comp (ref "R218")
      (value "3.3K")
      (footprint "RESC1005X40X25NL05T10")
      (description "CRCW04023K30FKEDHP")
      (fields (field (name "MANUFACTURER") "Vishay Dale"))
      (libsource (lib "Altium Content Vault") (part "RES"))
    )
    (comp (ref "R219")
      (value "3.3K")
      (footprint "RESC1005X40X25NL05T10")
      (description "CRCW04023K30FKEDHP")
      (fields (field (name "MANUFACTURER") "Vishay Dale"))
      (libsource (lib "Altium Content Vault") (part "RES"))
    )
    (comp (ref "R220")
      (value "3.3K")
      (footprint "RESC1005X40X25NL05T10")
      (description "CRCW04023K30FKEDHP")
      (fields (field (name "MANUFACTURER") "Vishay Dale"))
      (libsource (lib "Altium Content Vault") (part "RES"))
    )
    (comp (ref "R221")
      (value "3.3K")
      (footprint "RESC1005X40X25NL05T10")
      (description "CRCW04023K30FKEDHP")
      (fields (field (name "MANUFACTURER") "Vishay Dale"))
      (libsource (lib "Altium Content Vault") (part "RES"))
    )
    (comp (ref "R222")
      (value "3.3K")
      (footprint "RESC1005X40X25NL05T10")
      (description "CRCW04023K30FKEDHP")
      (fields (field (name "MANUFACTURER") "Vishay Dale"))
      (libsource (lib "Altium Content Vault") (part "RES"))
    )
    (comp (ref "R223")
      (value "3.3K")
      (footprint "RESC1005X40X25NL05T10")
      (description "CRCW04023K30FKEDHP")
      (fields (field (name "MANUFACTURER") "Vishay Dale"))
      (libsource (lib "Altium Content Vault") (part "RES"))
    )
    (comp (ref "R224")
      (value "3.3K")
      (footprint "RESC1005X40X25NL05T10")
      (description "CRCW04023K30FKEDHP")
      (fields (field (name "MANUFACTURER") "Vishay Dale"))
      (libsource (lib "Altium Content Vault") (part "RES"))
    )
    (comp (ref "SW10")
      (value "B3S-1000P")
      (footprint "FP-B3S-1000P-MFG")
      (description "SWITCH TACTILE SPST-NO 0.05A 24V")
      (libsource (lib "Altium Content Vault") (part "b8895f3f4cefb76e1819d2863dba89b"))
    )
    (comp (ref "SW11")
      (value "B3S-1000P")
      (footprint "FP-B3S-1000P-MFG")
      (description "SWITCH TACTILE SPST-NO 0.05A 24V")
      (libsource (lib "Altium Content Vault") (part "b8895f3f4cefb76e1819d2863dba89b"))
    )
    (comp (ref "SW12")
      (value "B3S-1000P")
      (footprint "FP-B3S-1000P-MFG")
      (description "SWITCH TACTILE SPST-NO 0.05A 24V")
      (libsource (lib "Altium Content Vault") (part "b8895f3f4cefb76e1819d2863dba89b"))
    )
    (comp (ref "SW13")
      (value "B3S-1000P")
      (footprint "FP-B3S-1000P-MFG")
      (description "SWITCH TACTILE SPST-NO 0.05A 24V")
      (libsource (lib "Altium Content Vault") (part "b8895f3f4cefb76e1819d2863dba89b"))
    )
    (comp (ref "SW14")
      (value "B3S-1000P")
      (footprint "FP-B3S-1000P-MFG")
      (description "SWITCH TACTILE SPST-NO 0.05A 24V")
      (libsource (lib "Altium Content Vault") (part "b8895f3f4cefb76e1819d2863dba89b"))
    )
    (comp (ref "SW15")
      (value "B3S-1000P")
      (footprint "FP-B3S-1000P-MFG")
      (description "SWITCH TACTILE SPST-NO 0.05A 24V")
      (libsource (lib "Altium Content Vault") (part "b8895f3f4cefb76e1819d2863dba89b"))
    )
    (comp (ref "SW16")
      (value "B3S-1000P")
      (footprint "FP-B3S-1000P-MFG")
      (description "SWITCH TACTILE SPST-NO 0.05A 24V")
      (libsource (lib "Altium Content Vault") (part "b8895f3f4cefb76e1819d2863dba89b"))
    )
    (comp (ref "SW17")
      (value "B3S-1000P")
      (footprint "FP-B3S-1000P-MFG")
      (description "SWITCH TACTILE SPST-NO 0.05A 24V")
      (libsource (lib "Altium Content Vault") (part "b8895f3f4cefb76e1819d2863dba89b"))
    )
  )
  (nets
    (net (code "1") (name "+3V3") (class "Default")
      (node (ref "C270") (pin "2") (pinfunction "2_2") (pintype "passive"))
      (node (ref "C272") (pin "2") (pinfunction "2_2") (pintype "passive"))
      (node (ref "C274") (pin "2") (pinfunction "2_2") (pintype "passive"))
      (node (ref "DS13") (pin "1") (pinfunction "A_1") (pintype "passive"))
      (node (ref "DS14") (pin "1") (pinfunction "A_1") (pintype "passive"))
      (node (ref "DS15") (pin "1") (pinfunction "A_1") (pintype "passive"))
      (node (ref "DS16") (pin "1") (pinfunction "A_1") (pintype "passive"))
      (node (ref "DS17") (pin "1") (pinfunction "A_1") (pintype "passive"))
      (node (ref "DS18") (pin "1") (pinfunction "A_1") (pintype "passive"))
      (node (ref "DS19") (pin "1") (pinfunction "A_1") (pintype "passive"))
      (node (ref "DS20") (pin "1") (pinfunction "A_1") (pintype "passive"))
      (node (ref "DS21") (pin "1") (pinfunction "A_1") (pintype "passive"))
      (node (ref "DS22") (pin "1") (pinfunction "A_1") (pintype "passive"))
      (node (ref "DS23") (pin "1") (pinfunction "A_1") (pintype "passive"))
      (node (ref "DS24") (pin "1") (pinfunction "A_1") (pintype "passive"))
      (node (ref "DS25") (pin "1") (pinfunction "A_1") (pintype "passive"))
      (node (ref "DS26") (pin "1") (pinfunction "A_1") (pintype "passive"))
      (node (ref "DS27") (pin "1") (pinfunction "A_1") (pintype "passive"))
      (node (ref "DS28") (pin "1") (pinfunction "A_1") (pintype "passive"))
      (node (ref "J10") (pin "1") (pinfunction "1_1") (pintype "passive"))
      (node (ref "J10") (pin "2") (pinfunction "2_2") (pintype "passive"))
      (node (ref "J11") (pin "1") (pinfunction "1_1") (pintype "passive"))
      (node (ref "J11") (pin "2") (pinfunction "2_2") (pintype "passive"))
      (node (ref "J12") (pin "1") (pinfunction "1_1") (pintype "passive"))
      (node (ref "J12") (pin "2") (pinfunction "2_2") (pintype "passive"))
      (node (ref "J13") (pin "1") (pinfunction "1_1") (pintype "passive"))
      (node (ref "J13") (pin "2") (pinfunction "2_2") (pintype "passive"))
      (node (ref "J14") (pin "1") (pinfunction "1_1") (pintype "passive"))
      (node (ref "J14") (pin "2") (pinfunction "2_2") (pintype "passive"))
      (node (ref "J15") (pin "1") (pinfunction "1_1") (pintype "passive"))
      (node (ref "J15") (pin "2") (pinfunction "2_2") (pintype "passive"))
      (node (ref "J16") (pin "1") (pinfunction "1_1") (pintype "passive"))
      (node (ref "J16") (pin "2") (pinfunction "2_2") (pintype "passive"))
      (node (ref "J6") (pin "1") (pinfunction "1_1") (pintype "passive"))
      (node (ref "J6") (pin "2") (pinfunction "2_2") (pintype "passive"))
      (node (ref "J7") (pin "1") (pinfunction "1_1") (pintype "passive"))
      (node (ref "J7") (pin "3") (pinfunction "3_3") (pintype "passive"))
      (node (ref "J7") (pin "5") (pinfunction "5_5") (pintype "passive"))
      (node (ref "J7") (pin "7") (pinfunction "7_7") (pintype "passive"))
      (node (ref "J8") (pin "1") (pinfunction "1_1") (pintype "passive"))
      (node (ref "J8") (pin "3") (pinfunction "3_3") (pintype "passive"))
      (node (ref "J8") (pin "5") (pinfunction "5_5") (pintype "passive"))
      (node (ref "J8") (pin "7") (pinfunction "7_7") (pintype "passive"))
      (node (ref "J9") (pin "1") (pinfunction "1_1") (pintype "passive"))
      (node (ref "J9") (pin "3") (pinfunction "3_3") (pintype "passive"))
      (node (ref "J9") (pin "5") (pinfunction "5_5") (pintype "passive"))
      (node (ref "J9") (pin "7") (pinfunction "7_7") (pintype "passive"))
      (node (ref "R153") (pin "2") (pinfunction "2_2") (pintype "passive"))
      (node (ref "R154") (pin "2") (pinfunction "2_2") (pintype "passive"))
      (node (ref "R155") (pin "2") (pinfunction "2_2") (pintype "passive"))
      (node (ref "R156") (pin "2") (pinfunction "2_2") (pintype "passive"))
      (node (ref "R157") (pin "2") (pinfunction "2_2") (pintype "passive"))
      (node (ref "R158") (pin "2") (pinfunction "2_2") (pintype "passive"))
      (node (ref "R159") (pin "2") (pinfunction "2_2") (pintype "passive"))
      (node (ref "R160") (pin "2") (pinfunction "2_2") (pintype "passive"))
    )
    (net (code "2") (name "+5") (class "Default")
      (node (ref "C271") (pin "2") (pinfunction "2_2") (pintype "passive"))
      (node (ref "C273") (pin "2") (pinfunction "2_2") (pintype "passive"))
      (node (ref "C275") (pin "2") (pinfunction "2_2") (pintype "passive"))
      (node (ref "J7") (pin "2") (pinfunction "2_2") (pintype "passive"))
      (node (ref "J7") (pin "4") (pinfunction "4_4") (pintype "passive"))
      (node (ref "J7") (pin "6") (pinfunction "6_6") (pintype "passive"))
      (node (ref "J7") (pin "8") (pinfunction "8_8") (pintype "passive"))
      (node (ref "J8") (pin "2") (pinfunction "2_2") (pintype "passive"))
      (node (ref "J8") (pin "4") (pinfunction "4_4") (pintype "passive"))
      (node (ref "J8") (pin "6") (pinfunction "6_6") (pintype "passive"))
      (node (ref "J8") (pin "8") (pinfunction "8_8") (pintype "passive"))
      (node (ref "J9") (pin "2") (pinfunction "2_2") (pintype "passive"))
      (node (ref "J9") (pin "4") (pinfunction "4_4") (pintype "passive"))
      (node (ref "J9") (pin "6") (pinfunction "6_6") (pintype "passive"))
      (node (ref "J9") (pin "8") (pinfunction "8_8") (pintype "passive"))
    )
    (net (code "3") (name "/FPGA0_LED0") (class "Default")
      (node (ref "Q9") (pin "1") (pinfunction "G_1") (pintype "passive"))
      (node (ref "R205") (pin "1") (pinfunction "1_1") (pintype "passive"))
    )
    (net (code "4") (name "/FPGA0_LED1") (class "Default")
      (node (ref "Q10") (pin "1") (pinfunction "G_1") (pintype "passive"))
      (node (ref "R206") (pin "1") (pinfunction "1_1") (pintype "passive"))
    )
    (net (code "5") (name "/FPGA0_LED2") (class "Default")
      (node (ref "Q11") (pin "1") (pinfunction "G_1") (pintype "passive"))
      (node (ref "R207") (pin "1") (pinfunction "1_1") (pintype "passive"))
    )
    (net (code "6") (name "/FPGA0_LED3") (class "Default")
      (node (ref "Q12") (pin "1") (pinfunction "G_1") (pintype "passive"))
      (node (ref "R208") (pin "1") (pinfunction "1_1") (pintype "passive"))
    )
    (net (code "7") (name "/FPGA0_LED4") (class "Default")
      (node (ref "Q17") (pin "1") (pinfunction "G_1") (pintype "passive"))
      (node (ref "R221") (pin "1") (pinfunction "1_1") (pintype "passive"))
    )
    (net (code "8") (name "/FPGA0_LED5") (class "Default")
      (node (ref "Q18") (pin "1") (pinfunction "G_1") (pintype "passive"))
      (node (ref "R222") (pin "1") (pinfunction "1_1") (pintype "passive"))
    )
    (net (code "9") (name "/FPGA0_LED6") (class "Default")
      (node (ref "Q19") (pin "1") (pinfunction "G_1") (pintype "passive"))
      (node (ref "R223") (pin "1") (pinfunction "1_1") (pintype "passive"))
    )
    (net (code "10") (name "/FPGA0_LED7") (class "Default")
      (node (ref "Q20") (pin "1") (pinfunction "G_1") (pintype "passive"))
      (node (ref "R224") (pin "1") (pinfunction "1_1") (pintype "passive"))
    )
    (net (code "12") (name "/FPGA0_PMOD0_IO0") (class "Default")
      (node (ref "J6") (pin "5") (pinfunction "5_5") (pintype "passive"))
    )
    (net (code "13") (name "/FPGA0_PMOD0_IO1") (class "Default")
      (node (ref "J6") (pin "7") (pinfunction "7_7") (pintype "passive"))
    )
    (net (code "14") (name "/FPGA0_PMOD0_IO2") (class "Default")
      (node (ref "J6") (pin "9") (pinfunction "9_9") (pintype "passive"))
    )
    (net (code "15") (name "/FPGA0_PMOD0_IO3") (class "Default")
      (node (ref "J6") (pin "11") (pinfunction "11_11") (pintype "passive"))
    )
    (net (code "16") (name "/FPGA0_PMOD0_IO4") (class "Default")
      (node (ref "J6") (pin "12") (pinfunction "12_12") (pintype "passive"))
    )
    (net (code "17") (name "/FPGA0_PMOD0_IO5") (class "Default")
      (node (ref "J6") (pin "10") (pinfunction "10_10") (pintype "passive"))
    )
    (net (code "18") (name "/FPGA0_PMOD0_IO6") (class "Default")
      (node (ref "J6") (pin "8") (pinfunction "8_8") (pintype "passive"))
    )
    (net (code "19") (name "/FPGA0_PMOD0_IO7") (class "Default")
      (node (ref "J6") (pin "6") (pinfunction "6_6") (pintype "passive"))
    )
    (net (code "21") (name "/FPGA0_PMOD1_IO0") (class "Default")
      (node (ref "J10") (pin "5") (pinfunction "5_5") (pintype "passive"))
    )
    (net (code "22") (name "/FPGA0_PMOD1_IO1") (class "Default")
      (node (ref "J10") (pin "7") (pinfunction "7_7") (pintype "passive"))
    )
    (net (code "23") (name "/FPGA0_PMOD1_IO2") (class "Default")
      (node (ref "J10") (pin "9") (pinfunction "9_9") (pintype "passive"))
    )
    (net (code "24") (name "/FPGA0_PMOD1_IO3") (class "Default")
      (node (ref "J10") (pin "11") (pinfunction "11_11") (pintype "passive"))
    )
    (net (code "25") (name "/FPGA0_PMOD1_IO4") (class "Default")
      (node (ref "J10") (pin "12") (pinfunction "12_12") (pintype "passive"))
    )
    (net (code "26") (name "/FPGA0_PMOD1_IO5") (class "Default")
      (node (ref "J10") (pin "10") (pinfunction "10_10") (pintype "passive"))
    )
    (net (code "27") (name "/FPGA0_PMOD1_IO6") (class "Default")
      (node (ref "J10") (pin "8") (pinfunction "8_8") (pintype "passive"))
    )
    (net (code "28") (name "/FPGA0_PMOD1_IO7") (class "Default")
      (node (ref "J10") (pin "6") (pinfunction "6_6") (pintype "passive"))
    )
    (net (code "30") (name "/FPGA0_PMOD2_IO0") (class "Default")
      (node (ref "J11") (pin "5") (pinfunction "5_5") (pintype "passive"))
    )
    (net (code "31") (name "/FPGA0_PMOD2_IO1") (class "Default")
      (node (ref "J11") (pin "7") (pinfunction "7_7") (pintype "passive"))
    )
    (net (code "32") (name "/FPGA0_PMOD2_IO2") (class "Default")
      (node (ref "J11") (pin "9") (pinfunction "9_9") (pintype "passive"))
    )
    (net (code "33") (name "/FPGA0_PMOD2_IO3") (class "Default")
      (node (ref "J11") (pin "11") (pinfunction "11_11") (pintype "passive"))
    )
    (net (code "34") (name "/FPGA0_PMOD2_IO4") (class "Default")
      (node (ref "J11") (pin "12") (pinfunction "12_12") (pintype "passive"))
    )
    (net (code "35") (name "/FPGA0_PMOD2_IO5") (class "Default")
      (node (ref "J11") (pin "10") (pinfunction "10_10") (pintype "passive"))
    )
    (net (code "36") (name "/FPGA0_PMOD2_IO6") (class "Default")
      (node (ref "J11") (pin "8") (pinfunction "8_8") (pintype "passive"))
    )
    (net (code "37") (name "/FPGA0_PMOD2_IO7") (class "Default")
      (node (ref "J11") (pin "6") (pinfunction "6_6") (pintype "passive"))
    )
    (net (code "39") (name "/FPGA0_PMOD3_IO0") (class "Default")
      (node (ref "J12") (pin "5") (pinfunction "5_5") (pintype "passive"))
    )
    (net (code "40") (name "/FPGA0_PMOD3_IO1") (class "Default")
      (node (ref "J12") (pin "7") (pinfunction "7_7") (pintype "passive"))
    )
    (net (code "41") (name "/FPGA0_PMOD3_IO2") (class "Default")
      (node (ref "J12") (pin "9") (pinfunction "9_9") (pintype "passive"))
    )
    (net (code "42") (name "/FPGA0_PMOD3_IO3") (class "Default")
      (node (ref "J12") (pin "11") (pinfunction "11_11") (pintype "passive"))
    )
    (net (code "43") (name "/FPGA0_PMOD3_IO4") (class "Default")
      (node (ref "J12") (pin "12") (pinfunction "12_12") (pintype "passive"))
    )
    (net (code "44") (name "/FPGA0_PMOD3_IO5") (class "Default")
      (node (ref "J12") (pin "10") (pinfunction "10_10") (pintype "passive"))
    )
    (net (code "45") (name "/FPGA0_PMOD3_IO6") (class "Default")
      (node (ref "J12") (pin "8") (pinfunction "8_8") (pintype "passive"))
    )
    (net (code "46") (name "/FPGA0_PMOD3_IO7") (class "Default")
      (node (ref "J12") (pin "6") (pinfunction "6_6") (pintype "passive"))
    )
    (net (code "48") (name "/FPGA1_LED0") (class "Default")
      (node (ref "Q5") (pin "1") (pinfunction "G_1") (pintype "passive"))
      (node (ref "R201") (pin "1") (pinfunction "1_1") (pintype "passive"))
    )
    (net (code "49") (name "/FPGA1_LED1") (class "Default")
      (node (ref "Q6") (pin "1") (pinfunction "G_1") (pintype "passive"))
      (node (ref "R202") (pin "1") (pinfunction "1_1") (pintype "passive"))
    )
    (net (code "50") (name "/FPGA1_LED2") (class "Default")
      (node (ref "Q7") (pin "1") (pinfunction "G_1") (pintype "passive"))
      (node (ref "R203") (pin "1") (pinfunction "1_1") (pintype "passive"))
    )
    (net (code "51") (name "/FPGA1_LED3") (class "Default")
      (node (ref "Q8") (pin "1") (pinfunction "G_1") (pintype "passive"))
      (node (ref "R204") (pin "1") (pinfunction "1_1") (pintype "passive"))
    )
    (net (code "52") (name "/FPGA1_LED4") (class "Default")
      (node (ref "Q13") (pin "1") (pinfunction "G_1") (pintype "passive"))
      (node (ref "R217") (pin "1") (pinfunction "1_1") (pintype "passive"))
    )
    (net (code "53") (name "/FPGA1_LED5") (class "Default")
      (node (ref "Q14") (pin "1") (pinfunction "G_1") (pintype "passive"))
      (node (ref "R218") (pin "1") (pinfunction "1_1") (pintype "passive"))
    )
    (net (code "54") (name "/FPGA1_LED6") (class "Default")
      (node (ref "Q15") (pin "1") (pinfunction "G_1") (pintype "passive"))
      (node (ref "R219") (pin "1") (pinfunction "1_1") (pintype "passive"))
    )
    (net (code "55") (name "/FPGA1_LED7") (class "Default")
      (node (ref "Q16") (pin "1") (pinfunction "G_1") (pintype "passive"))
      (node (ref "R220") (pin "1") (pinfunction "1_1") (pintype "passive"))
    )
    (net (code "57") (name "/FPGA1_PMOD0_BUFF_IO0") (class "Default")
      (node (ref "J13") (pin "5") (pinfunction "5_5") (pintype "passive"))
    )
    (net (code "58") (name "/FPGA1_PMOD0_BUFF_IO1") (class "Default")
      (node (ref "J13") (pin "7") (pinfunction "7_7") (pintype "passive"))
    )
    (net (code "59") (name "/FPGA1_PMOD0_BUFF_IO2") (class "Default")
      (node (ref "J13") (pin "9") (pinfunction "9_9") (pintype "passive"))
    )
    (net (code "60") (name "/FPGA1_PMOD0_BUFF_IO3") (class "Default")
      (node (ref "J13") (pin "11") (pinfunction "11_11") (pintype "passive"))
    )
    (net (code "61") (name "/FPGA1_PMOD0_BUFF_IO4") (class "Default")
      (node (ref "J13") (pin "12") (pinfunction "12_12") (pintype "passive"))
    )
    (net (code "62") (name "/FPGA1_PMOD0_BUFF_IO5") (class "Default")
      (node (ref "J13") (pin "10") (pinfunction "10_10") (pintype "passive"))
    )
    (net (code "63") (name "/FPGA1_PMOD0_BUFF_IO6") (class "Default")
      (node (ref "J13") (pin "8") (pinfunction "8_8") (pintype "passive"))
    )
    (net (code "64") (name "/FPGA1_PMOD0_BUFF_IO7") (class "Default")
      (node (ref "J13") (pin "6") (pinfunction "6_6") (pintype "passive"))
    )
    (net (code "66") (name "/FPGA1_PMOD1_BUFF_IO0") (class "Default")
      (node (ref "J14") (pin "5") (pinfunction "5_5") (pintype "passive"))
    )
    (net (code "67") (name "/FPGA1_PMOD1_BUFF_IO1") (class "Default")
      (node (ref "J14") (pin "7") (pinfunction "7_7") (pintype "passive"))
    )
    (net (code "68") (name "/FPGA1_PMOD1_BUFF_IO2") (class "Default")
      (node (ref "J14") (pin "9") (pinfunction "9_9") (pintype "passive"))
    )
    (net (code "69") (name "/FPGA1_PMOD1_BUFF_IO3") (class "Default")
      (node (ref "J14") (pin "11") (pinfunction "11_11") (pintype "passive"))
    )
    (net (code "70") (name "/FPGA1_PMOD1_BUFF_IO4") (class "Default")
      (node (ref "J14") (pin "12") (pinfunction "12_12") (pintype "passive"))
    )
    (net (code "71") (name "/FPGA1_PMOD1_BUFF_IO5") (class "Default")
      (node (ref "J14") (pin "10") (pinfunction "10_10") (pintype "passive"))
    )
    (net (code "72") (name "/FPGA1_PMOD1_BUFF_IO6") (class "Default")
      (node (ref "J14") (pin "8") (pinfunction "8_8") (pintype "passive"))
    )
    (net (code "73") (name "/FPGA1_PMOD1_BUFF_IO7") (class "Default")
      (node (ref "J14") (pin "6") (pinfunction "6_6") (pintype "passive"))
    )
    (net (code "75") (name "/FPGA1_PMOD2_BUFF_IO0") (class "Default")
      (node (ref "J15") (pin "5") (pinfunction "5_5") (pintype "passive"))
    )
    (net (code "76") (name "/FPGA1_PMOD2_BUFF_IO1") (class "Default")
      (node (ref "J15") (pin "7") (pinfunction "7_7") (pintype "passive"))
    )
    (net (code "77") (name "/FPGA1_PMOD2_BUFF_IO2") (class "Default")
      (node (ref "J15") (pin "9") (pinfunction "9_9") (pintype "passive"))
    )
    (net (code "78") (name "/FPGA1_PMOD2_BUFF_IO3") (class "Default")
      (node (ref "J15") (pin "11") (pinfunction "11_11") (pintype "passive"))
    )
    (net (code "79") (name "/FPGA1_PMOD2_BUFF_IO4") (class "Default")
      (node (ref "J15") (pin "12") (pinfunction "12_12") (pintype "passive"))
    )
    (net (code "80") (name "/FPGA1_PMOD2_BUFF_IO5") (class "Default")
      (node (ref "J15") (pin "10") (pinfunction "10_10") (pintype "passive"))
    )
    (net (code "81") (name "/FPGA1_PMOD2_BUFF_IO6") (class "Default")
      (node (ref "J15") (pin "8") (pinfunction "8_8") (pintype "passive"))
    )
    (net (code "82") (name "/FPGA1_PMOD2_BUFF_IO7") (class "Default")
      (node (ref "J15") (pin "6") (pinfunction "6_6") (pintype "passive"))
    )
    (net (code "84") (name "/FPGA1_PMOD3_BUFF_IO0") (class "Default")
      (node (ref "J16") (pin "5") (pinfunction "5_5") (pintype "passive"))
    )
    (net (code "85") (name "/FPGA1_PMOD3_BUFF_IO1") (class "Default")
      (node (ref "J16") (pin "7") (pinfunction "7_7") (pintype "passive"))
    )
    (net (code "86") (name "/FPGA1_PMOD3_BUFF_IO2") (class "Default")
      (node (ref "J16") (pin "9") (pinfunction "9_9") (pintype "passive"))
    )
    (net (code "87") (name "/FPGA1_PMOD3_BUFF_IO3") (class "Default")
      (node (ref "J16") (pin "11") (pinfunction "11_11") (pintype "passive"))
    )
    (net (code "88") (name "/FPGA1_PMOD3_BUFF_IO4") (class "Default")
      (node (ref "J16") (pin "12") (pinfunction "12_12") (pintype "passive"))
    )
    (net (code "89") (name "/FPGA1_PMOD3_BUFF_IO5") (class "Default")
      (node (ref "J16") (pin "10") (pinfunction "10_10") (pintype "passive"))
    )
    (net (code "90") (name "/FPGA1_PMOD3_BUFF_IO6") (class "Default")
      (node (ref "J16") (pin "8") (pinfunction "8_8") (pintype "passive"))
    )
    (net (code "91") (name "/FPGA1_PMOD3_BUFF_IO7") (class "Default")
      (node (ref "J16") (pin "6") (pinfunction "6_6") (pintype "passive"))
    )
    (net (code "93") (name "/USER_FPGA0_BUTTON0") (class "Default")
      (node (ref "R161") (pin "1") (pinfunction "1_1") (pintype "passive"))
    )
    (net (code "94") (name "/USER_FPGA0_BUTTON1") (class "Default")
      (node (ref "R169") (pin "1") (pinfunction "1_1") (pintype "passive"))
    )
    (net (code "95") (name "/USER_FPGA0_BUTTON2") (class "Default")
      (node (ref "R175") (pin "1") (pinfunction "1_1") (pintype "passive"))
    )
    (net (code "96") (name "/USER_FPGA0_BUTTON3") (class "Default")
      (node (ref "R183") (pin "1") (pinfunction "1_1") (pintype "passive"))
    )
    (net (code "98") (name "/USER_FPGA0_R_BUTTON0") (class "Default")
      (node (ref "C276") (pin "2") (pinfunction "2_2") (pintype "passive"))
      (node (ref "R153") (pin "1") (pinfunction "1_1") (pintype "passive"))
      (node (ref "R161") (pin "2") (pinfunction "2_2") (pintype "passive"))
      (node (ref "SW10") (pin "3") (pinfunction "3_3") (pintype "passive"))
      (node (ref "SW10") (pin "4") (pinfunction "4_4") (pintype "passive"))
    )
    (net (code "99") (name "/USER_FPGA0_R_BUTTON1") (class "Default")
      (node (ref "C278") (pin "2") (pinfunction "2_2") (pintype "passive"))
      (node (ref "R154") (pin "1") (pinfunction "1_1") (pintype "passive"))
      (node (ref "R169") (pin "2") (pinfunction "2_2") (pintype "passive"))
      (node (ref "SW12") (pin "3") (pinfunction "3_3") (pintype "passive"))
      (node (ref "SW12") (pin "4") (pinfunction "4_4") (pintype "passive"))
    )
    (net (code "100") (name "/USER_FPGA0_R_BUTTON2") (class "Default")
      (node (ref "C280") (pin "2") (pinfunction "2_2") (pintype "passive"))
      (node (ref "R155") (pin "1") (pinfunction "1_1") (pintype "passive"))
      (node (ref "R175") (pin "2") (pinfunction "2_2") (pintype "passive"))
      (node (ref "SW14") (pin "3") (pinfunction "3_3") (pintype "passive"))
      (node (ref "SW14") (pin "4") (pinfunction "4_4") (pintype "passive"))
    )
    (net (code "101") (name "/USER_FPGA0_R_BUTTON3") (class "Default")
      (node (ref "C282") (pin "2") (pinfunction "2_2") (pintype "passive"))
      (node (ref "R156") (pin "1") (pinfunction "1_1") (pintype "passive"))
      (node (ref "R183") (pin "2") (pinfunction "2_2") (pintype "passive"))
      (node (ref "SW16") (pin "3") (pinfunction "3_3") (pintype "passive"))
      (node (ref "SW16") (pin "4") (pinfunction "4_4") (pintype "passive"))
    )
    (net (code "102") (name "/USER_FPGA1_BUTTON0") (class "Default")
      (node (ref "R162") (pin "1") (pinfunction "1_1") (pintype "passive"))
    )
    (net (code "103") (name "/USER_FPGA1_BUTTON1") (class "Default")
      (node (ref "R170") (pin "1") (pinfunction "1_1") (pintype "passive"))
    )
    (net (code "104") (name "/USER_FPGA1_BUTTON2") (class "Default")
      (node (ref "R176") (pin "1") (pinfunction "1_1") (pintype "passive"))
    )
    (net (code "105") (name "/USER_FPGA1_BUTTON3") (class "Default")
      (node (ref "R184") (pin "1") (pinfunction "1_1") (pintype "passive"))
    )
    (net (code "107") (name "/USER_FPGA1_R_BUTTON0") (class "Default")
      (node (ref "C277") (pin "2") (pinfunction "2_2") (pintype "passive"))
      (node (ref "R157") (pin "1") (pinfunction "1_1") (pintype "passive"))
      (node (ref "R162") (pin "2") (pinfunction "2_2") (pintype "passive"))
      (node (ref "SW11") (pin "3") (pinfunction "3_3") (pintype "passive"))
      (node (ref "SW11") (pin "4") (pinfunction "4_4") (pintype "passive"))
    )
    (net (code "108") (name "/USER_FPGA1_R_BUTTON1") (class "Default")
      (node (ref "C279") (pin "2") (pinfunction "2_2") (pintype "passive"))
      (node (ref "R158") (pin "1") (pinfunction "1_1") (pintype "passive"))
      (node (ref "R170") (pin "2") (pinfunction "2_2") (pintype "passive"))
      (node (ref "SW13") (pin "3") (pinfunction "3_3") (pintype "passive"))
      (node (ref "SW13") (pin "4") (pinfunction "4_4") (pintype "passive"))
    )
    (net (code "109") (name "/USER_FPGA1_R_BUTTON2") (class "Default")
      (node (ref "C281") (pin "2") (pinfunction "2_2") (pintype "passive"))
      (node (ref "R159") (pin "1") (pinfunction "1_1") (pintype "passive"))
      (node (ref "R176") (pin "2") (pinfunction "2_2") (pintype "passive"))
      (node (ref "SW15") (pin "3") (pinfunction "3_3") (pintype "passive"))
      (node (ref "SW15") (pin "4") (pinfunction "4_4") (pintype "passive"))
    )
    (net (code "110") (name "/USER_FPGA1_R_BUTTON3") (class "Default")
      (node (ref "C283") (pin "2") (pinfunction "2_2") (pintype "passive"))
      (node (ref "R160") (pin "1") (pinfunction "1_1") (pintype "passive"))
      (node (ref "R184") (pin "2") (pinfunction "2_2") (pintype "passive"))
      (node (ref "SW17") (pin "3") (pinfunction "3_3") (pintype "passive"))
      (node (ref "SW17") (pin "4") (pinfunction "4_4") (pintype "passive"))
    )
    (net (code "111") (name "/USER_IOB0_BUFFER_IO0") (class "Default")
      (node (ref "J7") (pin "80") (pinfunction "80_80") (pintype "passive"))
    )
    (net (code "112") (name "/USER_IOB0_BUFFER_IO1") (class "Default")
      (node (ref "J7") (pin "77") (pinfunction "77_77") (pintype "passive"))
    )
    (net (code "113") (name "/USER_IOB0_BUFFER_IO2") (class "Default")
      (node (ref "J7") (pin "76") (pinfunction "76_76") (pintype "passive"))
    )
    (net (code "114") (name "/USER_IOB0_BUFFER_IO3") (class "Default")
      (node (ref "J7") (pin "73") (pinfunction "73_73") (pintype "passive"))
    )
    (net (code "115") (name "/USER_IOB0_BUFFER_IO4") (class "Default")
      (node (ref "J7") (pin "72") (pinfunction "72_72") (pintype "passive"))
    )
    (net (code "116") (name "/USER_IOB0_BUFFER_IO5") (class "Default")
      (node (ref "J7") (pin "69") (pinfunction "69_69") (pintype "passive"))
    )
    (net (code "117") (name "/USER_IOB0_BUFFER_IO6") (class "Default")
      (node (ref "J7") (pin "68") (pinfunction "68_68") (pintype "passive"))
    )
    (net (code "118") (name "/USER_IOB0_BUFFER_IO7") (class "Default")
      (node (ref "J7") (pin "65") (pinfunction "65_65") (pintype "passive"))
    )
    (net (code "119") (name "/USER_IOB0_BUFFER_IO8") (class "Default")
      (node (ref "J7") (pin "64") (pinfunction "64_64") (pintype "passive"))
    )
    (net (code "120") (name "/USER_IOB0_BUFFER_IO9") (class "Default")
      (node (ref "J7") (pin "61") (pinfunction "61_61") (pintype "passive"))
    )
    (net (code "121") (name "/USER_IOB0_BUFFER_IO10") (class "Default")
      (node (ref "J7") (pin "60") (pinfunction "60_60") (pintype "passive"))
    )
    (net (code "122") (name "/USER_IOB0_BUFFER_IO11") (class "Default")
      (node (ref "J7") (pin "57") (pinfunction "57_57") (pintype "passive"))
    )
    (net (code "123") (name "/USER_IOB0_BUFFER_IO12") (class "Default")
      (node (ref "J7") (pin "56") (pinfunction "56_56") (pintype "passive"))
    )
    (net (code "124") (name "/USER_IOB0_BUFFER_IO13") (class "Default")
      (node (ref "J7") (pin "53") (pinfunction "53_53") (pintype "passive"))
    )
    (net (code "125") (name "/USER_IOB0_BUFFER_IO14") (class "Default")
      (node (ref "J7") (pin "52") (pinfunction "52_52") (pintype "passive"))
    )
    (net (code "126") (name "/USER_IOB0_BUFFER_IO15") (class "Default")
      (node (ref "J7") (pin "49") (pinfunction "49_49") (pintype "passive"))
    )
    (net (code "127") (name "/USER_IOB0_BUFFER_IO16") (class "Default")
      (node (ref "J7") (pin "48") (pinfunction "48_48") (pintype "passive"))
    )
    (net (code "128") (name "/USER_IOB0_BUFFER_IO17") (class "Default")
      (node (ref "J7") (pin "45") (pinfunction "45_45") (pintype "passive"))
    )
    (net (code "129") (name "/USER_IOB0_BUFFER_IO18") (class "Default")
      (node (ref "J7") (pin "44") (pinfunction "44_44") (pintype "passive"))
    )
    (net (code "130") (name "/USER_IOB0_BUFFER_IO19") (class "Default")
      (node (ref "J7") (pin "41") (pinfunction "41_41") (pintype "passive"))
    )
    (net (code "131") (name "/USER_IOB0_BUFFER_IO20") (class "Default")
      (node (ref "J7") (pin "40") (pinfunction "40_40") (pintype "passive"))
    )
    (net (code "132") (name "/USER_IOB0_BUFFER_IO21") (class "Default")
      (node (ref "J7") (pin "37") (pinfunction "37_37") (pintype "passive"))
    )
    (net (code "133") (name "/USER_IOB0_BUFFER_IO22") (class "Default")
      (node (ref "J7") (pin "36") (pinfunction "36_36") (pintype "passive"))
    )
    (net (code "134") (name "/USER_IOB0_BUFFER_IO23") (class "Default")
      (node (ref "J7") (pin "33") (pinfunction "33_33") (pintype "passive"))
    )
    (net (code "135") (name "/USER_IOB0_BUFFER_IO24") (class "Default")
      (node (ref "J7") (pin "32") (pinfunction "32_32") (pintype "passive"))
    )
    (net (code "136") (name "/USER_IOB0_BUFFER_IO25") (class "Default")
      (node (ref "J7") (pin "29") (pinfunction "29_29") (pintype "passive"))
    )
    (net (code "137") (name "/USER_IOB0_BUFFER_IO26") (class "Default")
      (node (ref "J7") (pin "28") (pinfunction "28_28") (pintype "passive"))
    )
    (net (code "138") (name "/USER_IOB0_BUFFER_IO27") (class "Default")
      (node (ref "J7") (pin "25") (pinfunction "25_25") (pintype "passive"))
    )
    (net (code "139") (name "/USER_IOB0_BUFFER_IO28") (class "Default")
      (node (ref "J7") (pin "24") (pinfunction "24_24") (pintype "passive"))
    )
    (net (code "140") (name "/USER_IOB0_BUFFER_IO29") (class "Default")
      (node (ref "J7") (pin "21") (pinfunction "21_21") (pintype "passive"))
    )
    (net (code "141") (name "/USER_IOB0_BUFFER_IO30") (class "Default")
      (node (ref "J7") (pin "20") (pinfunction "20_20") (pintype "passive"))
    )
    (net (code "142") (name "/USER_IOB0_BUFFER_IO31") (class "Default")
      (node (ref "J7") (pin "17") (pinfunction "17_17") (pintype "passive"))
    )
    (net (code "143") (name "/USER_IOB0_BUFFER_IO32") (class "Default")
      (node (ref "J7") (pin "16") (pinfunction "16_16") (pintype "passive"))
    )
    (net (code "144") (name "/USER_IOB0_BUFFER_IO33") (class "Default")
      (node (ref "J7") (pin "13") (pinfunction "13_13") (pintype "passive"))
    )
    (net (code "145") (name "/USER_IOB0_BUFFER_IO34") (class "Default")
      (node (ref "J7") (pin "12") (pinfunction "12_12") (pintype "passive"))
    )
    (net (code "146") (name "/USER_IOB0_BUFFER_IO35") (class "Default")
      (node (ref "J7") (pin "9") (pinfunction "9_9") (pintype "passive"))
    )
    (net (code "147") (name "/USER_IOB0_BUFFER_IO36") (class "Default")
      (node (ref "J8") (pin "9") (pinfunction "9_9") (pintype "passive"))
    )
    (net (code "148") (name "/USER_IOB0_BUFFER_IO37") (class "Default")
      (node (ref "J8") (pin "12") (pinfunction "12_12") (pintype "passive"))
    )
    (net (code "149") (name "/USER_IOB0_BUFFER_IO38") (class "Default")
      (node (ref "J8") (pin "13") (pinfunction "13_13") (pintype "passive"))
    )
    (net (code "150") (name "/USER_IOB0_BUFFER_IO39") (class "Default")
      (node (ref "J8") (pin "16") (pinfunction "16_16") (pintype "passive"))
    )
    (net (code "151") (name "/USER_IOB0_BUFFER_IO40") (class "Default")
      (node (ref "J8") (pin "17") (pinfunction "17_17") (pintype "passive"))
    )
    (net (code "152") (name "/USER_IOB0_BUFFER_IO41") (class "Default")
      (node (ref "J8") (pin "20") (pinfunction "20_20") (pintype "passive"))
    )
    (net (code "153") (name "/USER_IOB0_BUFFER_IO42") (class "Default")
      (node (ref "J8") (pin "21") (pinfunction "21_21") (pintype "passive"))
    )
    (net (code "154") (name "/USER_IOB0_BUFFER_IO43") (class "Default")
      (node (ref "J8") (pin "24") (pinfunction "24_24") (pintype "passive"))
    )
    (net (code "155") (name "/USER_IOB0_BUFFER_IO44") (class "Default")
      (node (ref "J8") (pin "25") (pinfunction "25_25") (pintype "passive"))
    )
    (net (code "156") (name "/USER_IOB0_BUFFER_IO45") (class "Default")
      (node (ref "J8") (pin "28") (pinfunction "28_28") (pintype "passive"))
    )
    (net (code "157") (name "/USER_IOB0_BUFFER_IO46") (class "Default")
      (node (ref "J8") (pin "29") (pinfunction "29_29") (pintype "passive"))
    )
    (net (code "158") (name "/USER_IOB0_BUFFER_IO47") (class "Default")
      (node (ref "J8") (pin "32") (pinfunction "32_32") (pintype "passive"))
    )
    (net (code "160") (name "/USER_IOB1_BUFFER_IO0") (class "Default")
      (node (ref "J8") (pin "57") (pinfunction "57_57") (pintype "passive"))
    )
    (net (code "161") (name "/USER_IOB1_BUFFER_IO1") (class "Default")
      (node (ref "J8") (pin "60") (pinfunction "60_60") (pintype "passive"))
    )
    (net (code "162") (name "/USER_IOB1_BUFFER_IO2") (class "Default")
      (node (ref "J8") (pin "61") (pinfunction "61_61") (pintype "passive"))
    )
    (net (code "163") (name "/USER_IOB1_BUFFER_IO3") (class "Default")
      (node (ref "J8") (pin "64") (pinfunction "64_64") (pintype "passive"))
    )
    (net (code "164") (name "/USER_IOB1_BUFFER_IO4") (class "Default")
      (node (ref "J8") (pin "65") (pinfunction "65_65") (pintype "passive"))
    )
    (net (code "165") (name "/USER_IOB1_BUFFER_IO5") (class "Default")
      (node (ref "J8") (pin "68") (pinfunction "68_68") (pintype "passive"))
    )
    (net (code "166") (name "/USER_IOB1_BUFFER_IO6") (class "Default")
      (node (ref "J8") (pin "69") (pinfunction "69_69") (pintype "passive"))
    )
    (net (code "167") (name "/USER_IOB1_BUFFER_IO7") (class "Default")
      (node (ref "J8") (pin "72") (pinfunction "72_72") (pintype "passive"))
    )
    (net (code "168") (name "/USER_IOB1_BUFFER_IO8") (class "Default")
      (node (ref "J8") (pin "73") (pinfunction "73_73") (pintype "passive"))
    )
    (net (code "169") (name "/USER_IOB1_BUFFER_IO9") (class "Default")
      (node (ref "J8") (pin "76") (pinfunction "76_76") (pintype "passive"))
    )
    (net (code "170") (name "/USER_IOB1_BUFFER_IO10") (class "Default")
      (node (ref "J8") (pin "77") (pinfunction "77_77") (pintype "passive"))
    )
    (net (code "171") (name "/USER_IOB1_BUFFER_IO11") (class "Default")
      (node (ref "J8") (pin "80") (pinfunction "80_80") (pintype "passive"))
    )
    (net (code "172") (name "/USER_IOB1_BUFFER_IO12") (class "Default")
      (node (ref "J9") (pin "9") (pinfunction "9_9") (pintype "passive"))
    )
    (net (code "173") (name "/USER_IOB1_BUFFER_IO13") (class "Default")
      (node (ref "J9") (pin "12") (pinfunction "12_12") (pintype "passive"))
    )
    (net (code "174") (name "/USER_IOB1_BUFFER_IO14") (class "Default")
      (node (ref "J9") (pin "13") (pinfunction "13_13") (pintype "passive"))
    )
    (net (code "175") (name "/USER_IOB1_BUFFER_IO15") (class "Default")
      (node (ref "J9") (pin "16") (pinfunction "16_16") (pintype "passive"))
    )
    (net (code "176") (name "/USER_IOB1_BUFFER_IO16") (class "Default")
      (node (ref "J9") (pin "17") (pinfunction "17_17") (pintype "passive"))
    )
    (net (code "177") (name "/USER_IOB1_BUFFER_IO17") (class "Default")
      (node (ref "J9") (pin "20") (pinfunction "20_20") (pintype "passive"))
    )
    (net (code "178") (name "/USER_IOB1_BUFFER_IO18") (class "Default")
      (node (ref "J9") (pin "21") (pinfunction "21_21") (pintype "passive"))
    )
    (net (code "179") (name "/USER_IOB1_BUFFER_IO19") (class "Default")
      (node (ref "J9") (pin "24") (pinfunction "24_24") (pintype "passive"))
    )
    (net (code "180") (name "/USER_IOB1_BUFFER_IO20") (class "Default")
      (node (ref "J9") (pin "25") (pinfunction "25_25") (pintype "passive"))
    )
    (net (code "181") (name "/USER_IOB1_BUFFER_IO21") (class "Default")
      (node (ref "J9") (pin "28") (pinfunction "28_28") (pintype "passive"))
    )
    (net (code "182") (name "/USER_IOB1_BUFFER_IO22") (class "Default")
      (node (ref "J9") (pin "29") (pinfunction "29_29") (pintype "passive"))
    )
    (net (code "183") (name "/USER_IOB1_BUFFER_IO23") (class "Default")
      (node (ref "J9") (pin "32") (pinfunction "32_32") (pintype "passive"))
    )
    (net (code "184") (name "/USER_IOB1_BUFFER_IO24") (class "Default")
      (node (ref "J9") (pin "33") (pinfunction "33_33") (pintype "passive"))
    )
    (net (code "185") (name "/USER_IOB1_BUFFER_IO25") (class "Default")
      (node (ref "J9") (pin "36") (pinfunction "36_36") (pintype "passive"))
    )
    (net (code "186") (name "/USER_IOB1_BUFFER_IO26") (class "Default")
      (node (ref "J9") (pin "37") (pinfunction "37_37") (pintype "passive"))
    )
    (net (code "187") (name "/USER_IOB1_BUFFER_IO27") (class "Default")
      (node (ref "J9") (pin "40") (pinfunction "40_40") (pintype "passive"))
    )
    (net (code "188") (name "/USER_IOB1_BUFFER_IO28") (class "Default")
      (node (ref "J9") (pin "41") (pinfunction "41_41") (pintype "passive"))
    )
    (net (code "189") (name "/USER_IOB1_BUFFER_IO29") (class "Default")
      (node (ref "J9") (pin "44") (pinfunction "44_44") (pintype "passive"))
    )
    (net (code "190") (name "/USER_IOB1_BUFFER_IO30") (class "Default")
      (node (ref "J9") (pin "45") (pinfunction "45_45") (pintype "passive"))
    )
    (net (code "191") (name "/USER_IOB1_BUFFER_IO31") (class "Default")
      (node (ref "J9") (pin "48") (pinfunction "48_48") (pintype "passive"))
    )
    (net (code "192") (name "/USER_IOB1_BUFFER_IO32") (class "Default")
      (node (ref "J9") (pin "49") (pinfunction "49_49") (pintype "passive"))
    )
    (net (code "193") (name "/USER_IOB1_BUFFER_IO33") (class "Default")
      (node (ref "J9") (pin "52") (pinfunction "52_52") (pintype "passive"))
    )
    (net (code "194") (name "/USER_IOB1_BUFFER_IO34") (class "Default")
      (node (ref "J9") (pin "53") (pinfunction "53_53") (pintype "passive"))
    )
    (net (code "195") (name "/USER_IOB1_BUFFER_IO35") (class "Default")
      (node (ref "J9") (pin "56") (pinfunction "56_56") (pintype "passive"))
    )
    (net (code "196") (name "/USER_IOB1_BUFFER_IO36") (class "Default")
      (node (ref "J9") (pin "57") (pinfunction "57_57") (pintype "passive"))
    )
    (net (code "197") (name "/USER_IOB1_BUFFER_IO37") (class "Default")
      (node (ref "J9") (pin "60") (pinfunction "60_60") (pintype "passive"))
    )
    (net (code "198") (name "/USER_IOB1_BUFFER_IO38") (class "Default")
      (node (ref "J9") (pin "61") (pinfunction "61_61") (pintype "passive"))
    )
    (net (code "199") (name "/USER_IOB1_BUFFER_IO39") (class "Default")
      (node (ref "J9") (pin "64") (pinfunction "64_64") (pintype "passive"))
    )
    (net (code "200") (name "/USER_IOB1_BUFFER_IO40") (class "Default")
      (node (ref "J9") (pin "65") (pinfunction "65_65") (pintype "passive"))
    )
    (net (code "201") (name "/USER_IOB1_BUFFER_IO41") (class "Default")
      (node (ref "J9") (pin "68") (pinfunction "68_68") (pintype "passive"))
    )
    (net (code "202") (name "/USER_IOB1_BUFFER_IO42") (class "Default")
      (node (ref "J9") (pin "69") (pinfunction "69_69") (pintype "passive"))
    )
    (net (code "203") (name "/USER_IOB1_BUFFER_IO43") (class "Default")
      (node (ref "J9") (pin "72") (pinfunction "72_72") (pintype "passive"))
    )
    (net (code "204") (name "/USER_IOB1_BUFFER_IO44") (class "Default")
      (node (ref "J9") (pin "73") (pinfunction "73_73") (pintype "passive"))
    )
    (net (code "205") (name "/USER_IOB1_BUFFER_IO45") (class "Default")
      (node (ref "J9") (pin "76") (pinfunction "76_76") (pintype "passive"))
    )
    (net (code "206") (name "/USER_IOB1_BUFFER_IO46") (class "Default")
      (node (ref "J9") (pin "77") (pinfunction "77_77") (pintype "passive"))
    )
    (net (code "207") (name "/USER_IOB1_BUFFER_IO47") (class "Default")
      (node (ref "J9") (pin "80") (pinfunction "80_80") (pintype "passive"))
    )
    (net (code "209") (name "GND") (class "Default")
      (node (ref "C270") (pin "1") (pinfunction "1_1") (pintype "passive"))
      (node (ref "C271") (pin "1") (pinfunction "1_1") (pintype "passive"))
      (node (ref "C272") (pin "1") (pinfunction "1_1") (pintype "passive"))
      (node (ref "C273") (pin "1") (pinfunction "1_1") (pintype "passive"))
      (node (ref "C274") (pin "1") (pinfunction "1_1") (pintype "passive"))
      (node (ref "C275") (pin "1") (pinfunction "1_1") (pintype "passive"))
      (node (ref "C276") (pin "1") (pinfunction "1_1") (pintype "passive"))
      (node (ref "C277") (pin "1") (pinfunction "1_1") (pintype "passive"))
      (node (ref "C278") (pin "1") (pinfunction "1_1") (pintype "passive"))
      (node (ref "C279") (pin "1") (pinfunction "1_1") (pintype "passive"))
      (node (ref "C280") (pin "1") (pinfunction "1_1") (pintype "passive"))
      (node (ref "C281") (pin "1") (pinfunction "1_1") (pintype "passive"))
      (node (ref "C282") (pin "1") (pinfunction "1_1") (pintype "passive"))
      (node (ref "C283") (pin "1") (pinfunction "1_1") (pintype "passive"))
      (node (ref "J10") (pin "3") (pinfunction "3_3") (pintype "passive"))
      (node (ref "J10") (pin "4") (pinfunction "4_4") (pintype "passive"))
      (node (ref "J11") (pin "3") (pinfunction "3_3") (pintype "passive"))
      (node (ref "J11") (pin "4") (pinfunction "4_4") (pintype "passive"))
      (node (ref "J12") (pin "3") (pinfunction "3_3") (pintype "passive"))
      (node (ref "J12") (pin "4") (pinfunction "4_4") (pintype "passive"))
      (node (ref "J13") (pin "3") (pinfunction "3_3") (pintype "passive"))
      (node (ref "J13") (pin "4") (pinfunction "4_4") (pintype "passive"))
      (node (ref "J14") (pin "3") (pinfunction "3_3") (pintype "passive"))
      (node (ref "J14") (pin "4") (pinfunction "4_4") (pintype "passive"))
      (node (ref "J15") (pin "3") (pinfunction "3_3") (pintype "passive"))
      (node (ref "J15") (pin "4") (pinfunction "4_4") (pintype "passive"))
      (node (ref "J16") (pin "3") (pinfunction "3_3") (pintype "passive"))
      (node (ref "J16") (pin "4") (pinfunction "4_4") (pintype "passive"))
      (node (ref "J6") (pin "3") (pinfunction "3_3") (pintype "passive"))
      (node (ref "J6") (pin "4") (pinfunction "4_4") (pintype "passive"))
      (node (ref "J7") (pin "10") (pinfunction "10_10") (pintype "passive"))
      (node (ref "J7") (pin "11") (pinfunction "11_11") (pintype "passive"))
      (node (ref "J7") (pin "14") (pinfunction "14_14") (pintype "passive"))
      (node (ref "J7") (pin "15") (pinfunction "15_15") (pintype "passive"))
      (node (ref "J7") (pin "18") (pinfunction "18_18") (pintype "passive"))
      (node (ref "J7") (pin "19") (pinfunction "19_19") (pintype "passive"))
      (node (ref "J7") (pin "22") (pinfunction "22_22") (pintype "passive"))
      (node (ref "J7") (pin "23") (pinfunction "23_23") (pintype "passive"))
      (node (ref "J7") (pin "26") (pinfunction "26_26") (pintype "passive"))
      (node (ref "J7") (pin "27") (pinfunction "27_27") (pintype "passive"))
      (node (ref "J7") (pin "30") (pinfunction "30_30") (pintype "passive"))
      (node (ref "J7") (pin "31") (pinfunction "31_31") (pintype "passive"))
      (node (ref "J7") (pin "34") (pinfunction "34_34") (pintype "passive"))
      (node (ref "J7") (pin "35") (pinfunction "35_35") (pintype "passive"))
      (node (ref "J7") (pin "38") (pinfunction "38_38") (pintype "passive"))
      (node (ref "J7") (pin "39") (pinfunction "39_39") (pintype "passive"))
      (node (ref "J7") (pin "42") (pinfunction "42_42") (pintype "passive"))
      (node (ref "J7") (pin "43") (pinfunction "43_43") (pintype "passive"))
      (node (ref "J7") (pin "46") (pinfunction "46_46") (pintype "passive"))
      (node (ref "J7") (pin "47") (pinfunction "47_47") (pintype "passive"))
      (node (ref "J7") (pin "50") (pinfunction "50_50") (pintype "passive"))
      (node (ref "J7") (pin "51") (pinfunction "51_51") (pintype "passive"))
      (node (ref "J7") (pin "54") (pinfunction "54_54") (pintype "passive"))
      (node (ref "J7") (pin "55") (pinfunction "55_55") (pintype "passive"))
      (node (ref "J7") (pin "58") (pinfunction "58_58") (pintype "passive"))
      (node (ref "J7") (pin "59") (pinfunction "59_59") (pintype "passive"))
      (node (ref "J7") (pin "62") (pinfunction "62_62") (pintype "passive"))
      (node (ref "J7") (pin "63") (pinfunction "63_63") (pintype "passive"))
      (node (ref "J7") (pin "66") (pinfunction "66_66") (pintype "passive"))
      (node (ref "J7") (pin "67") (pinfunction "67_67") (pintype "passive"))
      (node (ref "J7") (pin "70") (pinfunction "70_70") (pintype "passive"))
      (node (ref "J7") (pin "71") (pinfunction "71_71") (pintype "passive"))
      (node (ref "J7") (pin "74") (pinfunction "74_74") (pintype "passive"))
      (node (ref "J7") (pin "75") (pinfunction "75_75") (pintype "passive"))
      (node (ref "J7") (pin "78") (pinfunction "78_78") (pintype "passive"))
      (node (ref "J7") (pin "79") (pinfunction "79_79") (pintype "passive"))
      (node (ref "J8") (pin "10") (pinfunction "10_10") (pintype "passive"))
      (node (ref "J8") (pin "11") (pinfunction "11_11") (pintype "passive"))
      (node (ref "J8") (pin "14") (pinfunction "14_14") (pintype "passive"))
      (node (ref "J8") (pin "15") (pinfunction "15_15") (pintype "passive"))
      (node (ref "J8") (pin "18") (pinfunction "18_18") (pintype "passive"))
      (node (ref "J8") (pin "19") (pinfunction "19_19") (pintype "passive"))
      (node (ref "J8") (pin "22") (pinfunction "22_22") (pintype "passive"))
      (node (ref "J8") (pin "23") (pinfunction "23_23") (pintype "passive"))
      (node (ref "J8") (pin "26") (pinfunction "26_26") (pintype "passive"))
      (node (ref "J8") (pin "27") (pinfunction "27_27") (pintype "passive"))
      (node (ref "J8") (pin "30") (pinfunction "30_30") (pintype "passive"))
      (node (ref "J8") (pin "31") (pinfunction "31_31") (pintype "passive"))
      (node (ref "J8") (pin "33") (pinfunction "33_33") (pintype "passive"))
      (node (ref "J8") (pin "34") (pinfunction "34_34") (pintype "passive"))
      (node (ref "J8") (pin "35") (pinfunction "35_35") (pintype "passive"))
      (node (ref "J8") (pin "36") (pinfunction "36_36") (pintype "passive"))
      (node (ref "J8") (pin "37") (pinfunction "37_37") (pintype "passive"))
      (node (ref "J8") (pin "38") (pinfunction "38_38") (pintype "passive"))
      (node (ref "J8") (pin "39") (pinfunction "39_39") (pintype "passive"))
      (node (ref "J8") (pin "40") (pinfunction "40_40") (pintype "passive"))
      (node (ref "J8") (pin "41") (pinfunction "41_41") (pintype "passive"))
      (node (ref "J8") (pin "42") (pinfunction "42_42") (pintype "passive"))
      (node (ref "J8") (pin "43") (pinfunction "43_43") (pintype "passive"))
      (node (ref "J8") (pin "44") (pinfunction "44_44") (pintype "passive"))
      (node (ref "J8") (pin "45") (pinfunction "45_45") (pintype "passive"))
      (node (ref "J8") (pin "46") (pinfunction "46_46") (pintype "passive"))
      (node (ref "J8") (pin "47") (pinfunction "47_47") (pintype "passive"))
      (node (ref "J8") (pin "48") (pinfunction "48_48") (pintype "passive"))
      (node (ref "J8") (pin "49") (pinfunction "49_49") (pintype "passive"))
      (node (ref "J8") (pin "50") (pinfunction "50_50") (pintype "passive"))
      (node (ref "J8") (pin "51") (pinfunction "51_51") (pintype "passive"))
      (node (ref "J8") (pin "52") (pinfunction "52_52") (pintype "passive"))
      (node (ref "J8") (pin "53") (pinfunction "53_53") (pintype "passive"))
      (node (ref "J8") (pin "54") (pinfunction "54_54") (pintype "passive"))
      (node (ref "J8") (pin "55") (pinfunction "55_55") (pintype "passive"))
      (node (ref "J8") (pin "56") (pinfunction "56_56") (pintype "passive"))
      (node (ref "J8") (pin "58") (pinfunction "58_58") (pintype "passive"))
      (node (ref "J8") (pin "59") (pinfunction "59_59") (pintype "passive"))
      (node (ref "J8") (pin "62") (pinfunction "62_62") (pintype "passive"))
      (node (ref "J8") (pin "63") (pinfunction "63_63") (pintype "passive"))
      (node (ref "J8") (pin "66") (pinfunction "66_66") (pintype "passive"))
      (node (ref "J8") (pin "67") (pinfunction "67_67") (pintype "passive"))
      (node (ref "J8") (pin "70") (pinfunction "70_70") (pintype "passive"))
      (node (ref "J8") (pin "71") (pinfunction "71_71") (pintype "passive"))
      (node (ref "J8") (pin "74") (pinfunction "74_74") (pintype "passive"))
      (node (ref "J8") (pin "75") (pinfunction "75_75") (pintype "passive"))
      (node (ref "J8") (pin "78") (pinfunction "78_78") (pintype "passive"))
      (node (ref "J8") (pin "79") (pinfunction "79_79") (pintype "passive"))
      (node (ref "J9") (pin "10") (pinfunction "10_10") (pintype "passive"))
      (node (ref "J9") (pin "11") (pinfunction "11_11") (pintype "passive"))
      (node (ref "J9") (pin "14") (pinfunction "14_14") (pintype "passive"))
      (node (ref "J9") (pin "15") (pinfunction "15_15") (pintype "passive"))
      (node (ref "J9") (pin "18") (pinfunction "18_18") (pintype "passive"))
      (node (ref "J9") (pin "19") (pinfunction "19_19") (pintype "passive"))
      (node (ref "J9") (pin "22") (pinfunction "22_22") (pintype "passive"))
      (node (ref "J9") (pin "23") (pinfunction "23_23") (pintype "passive"))
      (node (ref "J9") (pin "26") (pinfunction "26_26") (pintype "passive"))
      (node (ref "J9") (pin "27") (pinfunction "27_27") (pintype "passive"))
      (node (ref "J9") (pin "30") (pinfunction "30_30") (pintype "passive"))
      (node (ref "J9") (pin "31") (pinfunction "31_31") (pintype "passive"))
      (node (ref "J9") (pin "34") (pinfunction "34_34") (pintype "passive"))
      (node (ref "J9") (pin "35") (pinfunction "35_35") (pintype "passive"))
      (node (ref "J9") (pin "38") (pinfunction "38_38") (pintype "passive"))
      (node (ref "J9") (pin "39") (pinfunction "39_39") (pintype "passive"))
      (node (ref "J9") (pin "42") (pinfunction "42_42") (pintype "passive"))
      (node (ref "J9") (pin "43") (pinfunction "43_43") (pintype "passive"))
      (node (ref "J9") (pin "46") (pinfunction "46_46") (pintype "passive"))
      (node (ref "J9") (pin "47") (pinfunction "47_47") (pintype "passive"))
      (node (ref "J9") (pin "50") (pinfunction "50_50") (pintype "passive"))
      (node (ref "J9") (pin "51") (pinfunction "51_51") (pintype "passive"))
      (node (ref "J9") (pin "54") (pinfunction "54_54") (pintype "passive"))
      (node (ref "J9") (pin "55") (pinfunction "55_55") (pintype "passive"))
      (node (ref "J9") (pin "58") (pinfunction "58_58") (pintype "passive"))
      (node (ref "J9") (pin "59") (pinfunction "59_59") (pintype "passive"))
      (node (ref "J9") (pin "62") (pinfunction "62_62") (pintype "passive"))
      (node (ref "J9") (pin "63") (pinfunction "63_63") (pintype "passive"))
      (node (ref "J9") (pin "66") (pinfunction "66_66") (pintype "passive"))
      (node (ref "J9") (pin "67") (pinfunction "67_67") (pintype "passive"))
      (node (ref "J9") (pin "70") (pinfunction "70_70") (pintype "passive"))
      (node (ref "J9") (pin "71") (pinfunction "71_71") (pintype "passive"))
      (node (ref "J9") (pin "74") (pinfunction "74_74") (pintype "passive"))
      (node (ref "J9") (pin "75") (pinfunction "75_75") (pintype "passive"))
      (node (ref "J9") (pin "78") (pinfunction "78_78") (pintype "passive"))
      (node (ref "J9") (pin "79") (pinfunction "79_79") (pintype "passive"))
      (node (ref "Q10") (pin "2") (pinfunction "S_2") (pintype "passive"))
      (node (ref "Q11") (pin "2") (pinfunction "S_2") (pintype "passive"))
      (node (ref "Q12") (pin "2") (pinfunction "S_2") (pintype "passive"))
      (node (ref "Q13") (pin "2") (pinfunction "S_2") (pintype "passive"))
      (node (ref "Q14") (pin "2") (pinfunction "S_2") (pintype "passive"))
      (node (ref "Q15") (pin "2") (pinfunction "S_2") (pintype "passive"))
      (node (ref "Q16") (pin "2") (pinfunction "S_2") (pintype "passive"))
      (node (ref "Q17") (pin "2") (pinfunction "S_2") (pintype "passive"))
      (node (ref "Q18") (pin "2") (pinfunction "S_2") (pintype "passive"))
      (node (ref "Q19") (pin "2") (pinfunction "S_2") (pintype "passive"))
      (node (ref "Q20") (pin "2") (pinfunction "S_2") (pintype "passive"))
      (node (ref "Q5") (pin "2") (pinfunction "S_2") (pintype "passive"))
      (node (ref "Q6") (pin "2") (pinfunction "S_2") (pintype "passive"))
      (node (ref "Q7") (pin "2") (pinfunction "S_2") (pintype "passive"))
      (node (ref "Q8") (pin "2") (pinfunction "S_2") (pintype "passive"))
      (node (ref "Q9") (pin "2") (pinfunction "S_2") (pintype "passive"))
      (node (ref "R201") (pin "2") (pinfunction "2_2") (pintype "passive"))
      (node (ref "R202") (pin "2") (pinfunction "2_2") (pintype "passive"))
      (node (ref "R203") (pin "2") (pinfunction "2_2") (pintype "passive"))
      (node (ref "R204") (pin "2") (pinfunction "2_2") (pintype "passive"))
      (node (ref "R205") (pin "2") (pinfunction "2_2") (pintype "passive"))
      (node (ref "R206") (pin "2") (pinfunction "2_2") (pintype "passive"))
      (node (ref "R207") (pin "2") (pinfunction "2_2") (pintype "passive"))
      (node (ref "R208") (pin "2") (pinfunction "2_2") (pintype "passive"))
      (node (ref "R217") (pin "2") (pinfunction "2_2") (pintype "passive"))
      (node (ref "R218") (pin "2") (pinfunction "2_2") (pintype "passive"))
      (node (ref "R219") (pin "2") (pinfunction "2_2") (pintype "passive"))
      (node (ref "R220") (pin "2") (pinfunction "2_2") (pintype "passive"))
      (node (ref "R221") (pin "2") (pinfunction "2_2") (pintype "passive"))
      (node (ref "R222") (pin "2") (pinfunction "2_2") (pintype "passive"))
      (node (ref "R223") (pin "2") (pinfunction "2_2") (pintype "passive"))
      (node (ref "R224") (pin "2") (pinfunction "2_2") (pintype "passive"))
      (node (ref "SW10") (pin "1") (pinfunction "1_1") (pintype "passive"))
      (node (ref "SW10") (pin "2") (pinfunction "2_2") (pintype "passive"))
      (node (ref "SW11") (pin "1") (pinfunction "1_1") (pintype "passive"))
      (node (ref "SW11") (pin "2") (pinfunction "2_2") (pintype "passive"))
      (node (ref "SW12") (pin "1") (pinfunction "1_1") (pintype "passive"))
      (node (ref "SW12") (pin "2") (pinfunction "2_2") (pintype "passive"))
      (node (ref "SW13") (pin "1") (pinfunction "1_1") (pintype "passive"))
      (node (ref "SW13") (pin "2") (pinfunction "2_2") (pintype "passive"))
      (node (ref "SW14") (pin "1") (pinfunction "1_1") (pintype "passive"))
      (node (ref "SW14") (pin "2") (pinfunction "2_2") (pintype "passive"))
      (node (ref "SW15") (pin "1") (pinfunction "1_1") (pintype "passive"))
      (node (ref "SW15") (pin "2") (pinfunction "2_2") (pintype "passive"))
      (node (ref "SW16") (pin "1") (pinfunction "1_1") (pintype "passive"))
      (node (ref "SW16") (pin "2") (pinfunction "2_2") (pintype "passive"))
      (node (ref "SW17") (pin "1") (pinfunction "1_1") (pintype "passive"))
      (node (ref "SW17") (pin "2") (pinfunction "2_2") (pintype "passive"))
    )
    (net (code "210") (name "Net-(DS13-K)") (class "Default")
      (node (ref "DS13") (pin "2") (pinfunction "K_2") (pintype "passive"))
      (node (ref "R193") (pin "2") (pinfunction "2_2") (pintype "passive"))
    )
    (net (code "211") (name "Net-(DS14-K)") (class "Default")
      (node (ref "DS14") (pin "2") (pinfunction "K_2") (pintype "passive"))
      (node (ref "R194") (pin "2") (pinfunction "2_2") (pintype "passive"))
    )
    (net (code "212") (name "Net-(DS15-K)") (class "Default")
      (node (ref "DS15") (pin "2") (pinfunction "K_2") (pintype "passive"))
      (node (ref "R195") (pin "2") (pinfunction "2_2") (pintype "passive"))
    )
    (net (code "213") (name "Net-(DS16-K)") (class "Default")
      (node (ref "DS16") (pin "2") (pinfunction "K_2") (pintype "passive"))
      (node (ref "R196") (pin "2") (pinfunction "2_2") (pintype "passive"))
    )
    (net (code "214") (name "Net-(DS17-K)") (class "Default")
      (node (ref "DS17") (pin "2") (pinfunction "K_2") (pintype "passive"))
      (node (ref "R197") (pin "2") (pinfunction "2_2") (pintype "passive"))
    )
    (net (code "215") (name "Net-(DS18-K)") (class "Default")
      (node (ref "DS18") (pin "2") (pinfunction "K_2") (pintype "passive"))
      (node (ref "R198") (pin "2") (pinfunction "2_2") (pintype "passive"))
    )
    (net (code "216") (name "Net-(DS19-K)") (class "Default")
      (node (ref "DS19") (pin "2") (pinfunction "K_2") (pintype "passive"))
      (node (ref "R199") (pin "2") (pinfunction "2_2") (pintype "passive"))
    )
    (net (code "217") (name "Net-(DS20-K)") (class "Default")
      (node (ref "DS20") (pin "2") (pinfunction "K_2") (pintype "passive"))
      (node (ref "R200") (pin "2") (pinfunction "2_2") (pintype "passive"))
    )
    (net (code "218") (name "Net-(DS21-K)") (class "Default")
      (node (ref "DS21") (pin "2") (pinfunction "K_2") (pintype "passive"))
      (node (ref "R209") (pin "2") (pinfunction "2_2") (pintype "passive"))
    )
    (net (code "219") (name "Net-(DS22-K)") (class "Default")
      (node (ref "DS22") (pin "2") (pinfunction "K_2") (pintype "passive"))
      (node (ref "R210") (pin "2") (pinfunction "2_2") (pintype "passive"))
    )
    (net (code "220") (name "Net-(DS23-K)") (class "Default")
      (node (ref "DS23") (pin "2") (pinfunction "K_2") (pintype "passive"))
      (node (ref "R211") (pin "2") (pinfunction "2_2") (pintype "passive"))
    )
    (net (code "221") (name "Net-(DS24-K)") (class "Default")
      (node (ref "DS24") (pin "2") (pinfunction "K_2") (pintype "passive"))
      (node (ref "R212") (pin "2") (pinfunction "2_2") (pintype "passive"))
    )
    (net (code "222") (name "Net-(DS25-K)") (class "Default")
      (node (ref "DS25") (pin "2") (pinfunction "K_2") (pintype "passive"))
      (node (ref "R213") (pin "2") (pinfunction "2_2") (pintype "passive"))
    )
    (net (code "223") (name "Net-(DS26-K)") (class "Default")
      (node (ref "DS26") (pin "2") (pinfunction "K_2") (pintype "passive"))
      (node (ref "R214") (pin "2") (pinfunction "2_2") (pintype "passive"))
    )
    (net (code "224") (name "Net-(DS27-K)") (class "Default")
      (node (ref "DS27") (pin "2") (pinfunction "K_2") (pintype "passive"))
      (node (ref "R215") (pin "2") (pinfunction "2_2") (pintype "passive"))
    )
    (net (code "225") (name "Net-(DS28-K)") (class "Default")
      (node (ref "DS28") (pin "2") (pinfunction "K_2") (pintype "passive"))
      (node (ref "R216") (pin "2") (pinfunction "2_2") (pintype "passive"))
    )
    (net (code "226") (name "Net-(Q5-D)") (class "Default")
      (node (ref "Q5") (pin "3") (pinfunction "D_3") (pintype "passive"))
      (node (ref "R193") (pin "1") (pinfunction "1_1") (pintype "passive"))
    )
    (net (code "227") (name "Net-(Q6-D)") (class "Default")
      (node (ref "Q6") (pin "3") (pinfunction "D_3") (pintype "passive"))
      (node (ref "R194") (pin "1") (pinfunction "1_1") (pintype "passive"))
    )
    (net (code "228") (name "Net-(Q7-D)") (class "Default")
      (node (ref "Q7") (pin "3") (pinfunction "D_3") (pintype "passive"))
      (node (ref "R195") (pin "1") (pinfunction "1_1") (pintype "passive"))
    )
    (net (code "229") (name "Net-(Q8-D)") (class "Default")
      (node (ref "Q8") (pin "3") (pinfunction "D_3") (pintype "passive"))
      (node (ref "R196") (pin "1") (pinfunction "1_1") (pintype "passive"))
    )
    (net (code "230") (name "Net-(Q9-D)") (class "Default")
      (node (ref "Q9") (pin "3") (pinfunction "D_3") (pintype "passive"))
      (node (ref "R197") (pin "1") (pinfunction "1_1") (pintype "passive"))
    )
    (net (code "231") (name "Net-(Q10-D)") (class "Default")
      (node (ref "Q10") (pin "3") (pinfunction "D_3") (pintype "passive"))
      (node (ref "R198") (pin "1") (pinfunction "1_1") (pintype "passive"))
    )
    (net (code "232") (name "Net-(Q11-D)") (class "Default")
      (node (ref "Q11") (pin "3") (pinfunction "D_3") (pintype "passive"))
      (node (ref "R199") (pin "1") (pinfunction "1_1") (pintype "passive"))
    )
    (net (code "233") (name "Net-(Q12-D)") (class "Default")
      (node (ref "Q12") (pin "3") (pinfunction "D_3") (pintype "passive"))
      (node (ref "R200") (pin "1") (pinfunction "1_1") (pintype "passive"))
    )
    (net (code "234") (name "Net-(Q13-D)") (class "Default")
      (node (ref "Q13") (pin "3") (pinfunction "D_3") (pintype "passive"))
      (node (ref "R209") (pin "1") (pinfunction "1_1") (pintype "passive"))
    )
    (net (code "235") (name "Net-(Q14-D)") (class "Default")
      (node (ref "Q14") (pin "3") (pinfunction "D_3") (pintype "passive"))
      (node (ref "R210") (pin "1") (pinfunction "1_1") (pintype "passive"))
    )
    (net (code "236") (name "Net-(Q15-D)") (class "Default")
      (node (ref "Q15") (pin "3") (pinfunction "D_3") (pintype "passive"))
      (node (ref "R211") (pin "1") (pinfunction "1_1") (pintype "passive"))
    )
    (net (code "237") (name "Net-(Q16-D)") (class "Default")
      (node (ref "Q16") (pin "3") (pinfunction "D_3") (pintype "passive"))
      (node (ref "R212") (pin "1") (pinfunction "1_1") (pintype "passive"))
    )
    (net (code "238") (name "Net-(Q17-D)") (class "Default")
      (node (ref "Q17") (pin "3") (pinfunction "D_3") (pintype "passive"))
      (node (ref "R213") (pin "1") (pinfunction "1_1") (pintype "passive"))
    )
    (net (code "239") (name "Net-(Q18-D)") (class "Default")
      (node (ref "Q18") (pin "3") (pinfunction "D_3") (pintype "passive"))
      (node (ref "R214") (pin "1") (pinfunction "1_1") (pintype "passive"))
    )
    (net (code "240") (name "Net-(Q19-D)") (class "Default")
      (node (ref "Q19") (pin "3") (pinfunction "D_3") (pintype "passive"))
      (node (ref "R215") (pin "1") (pinfunction "1_1") (pintype "passive"))
    )
    (net (code "241") (name "Net-(Q20-D)") (class "Default")
      (node (ref "Q20") (pin "3") (pinfunction "D_3") (pintype "passive"))
      (node (ref "R216") (pin "1") (pinfunction "1_1") (pintype "passive"))
    )
  )
)
